# Motors_Drivers.net
KiCad netlist of a schematic drawn in Altium Designer
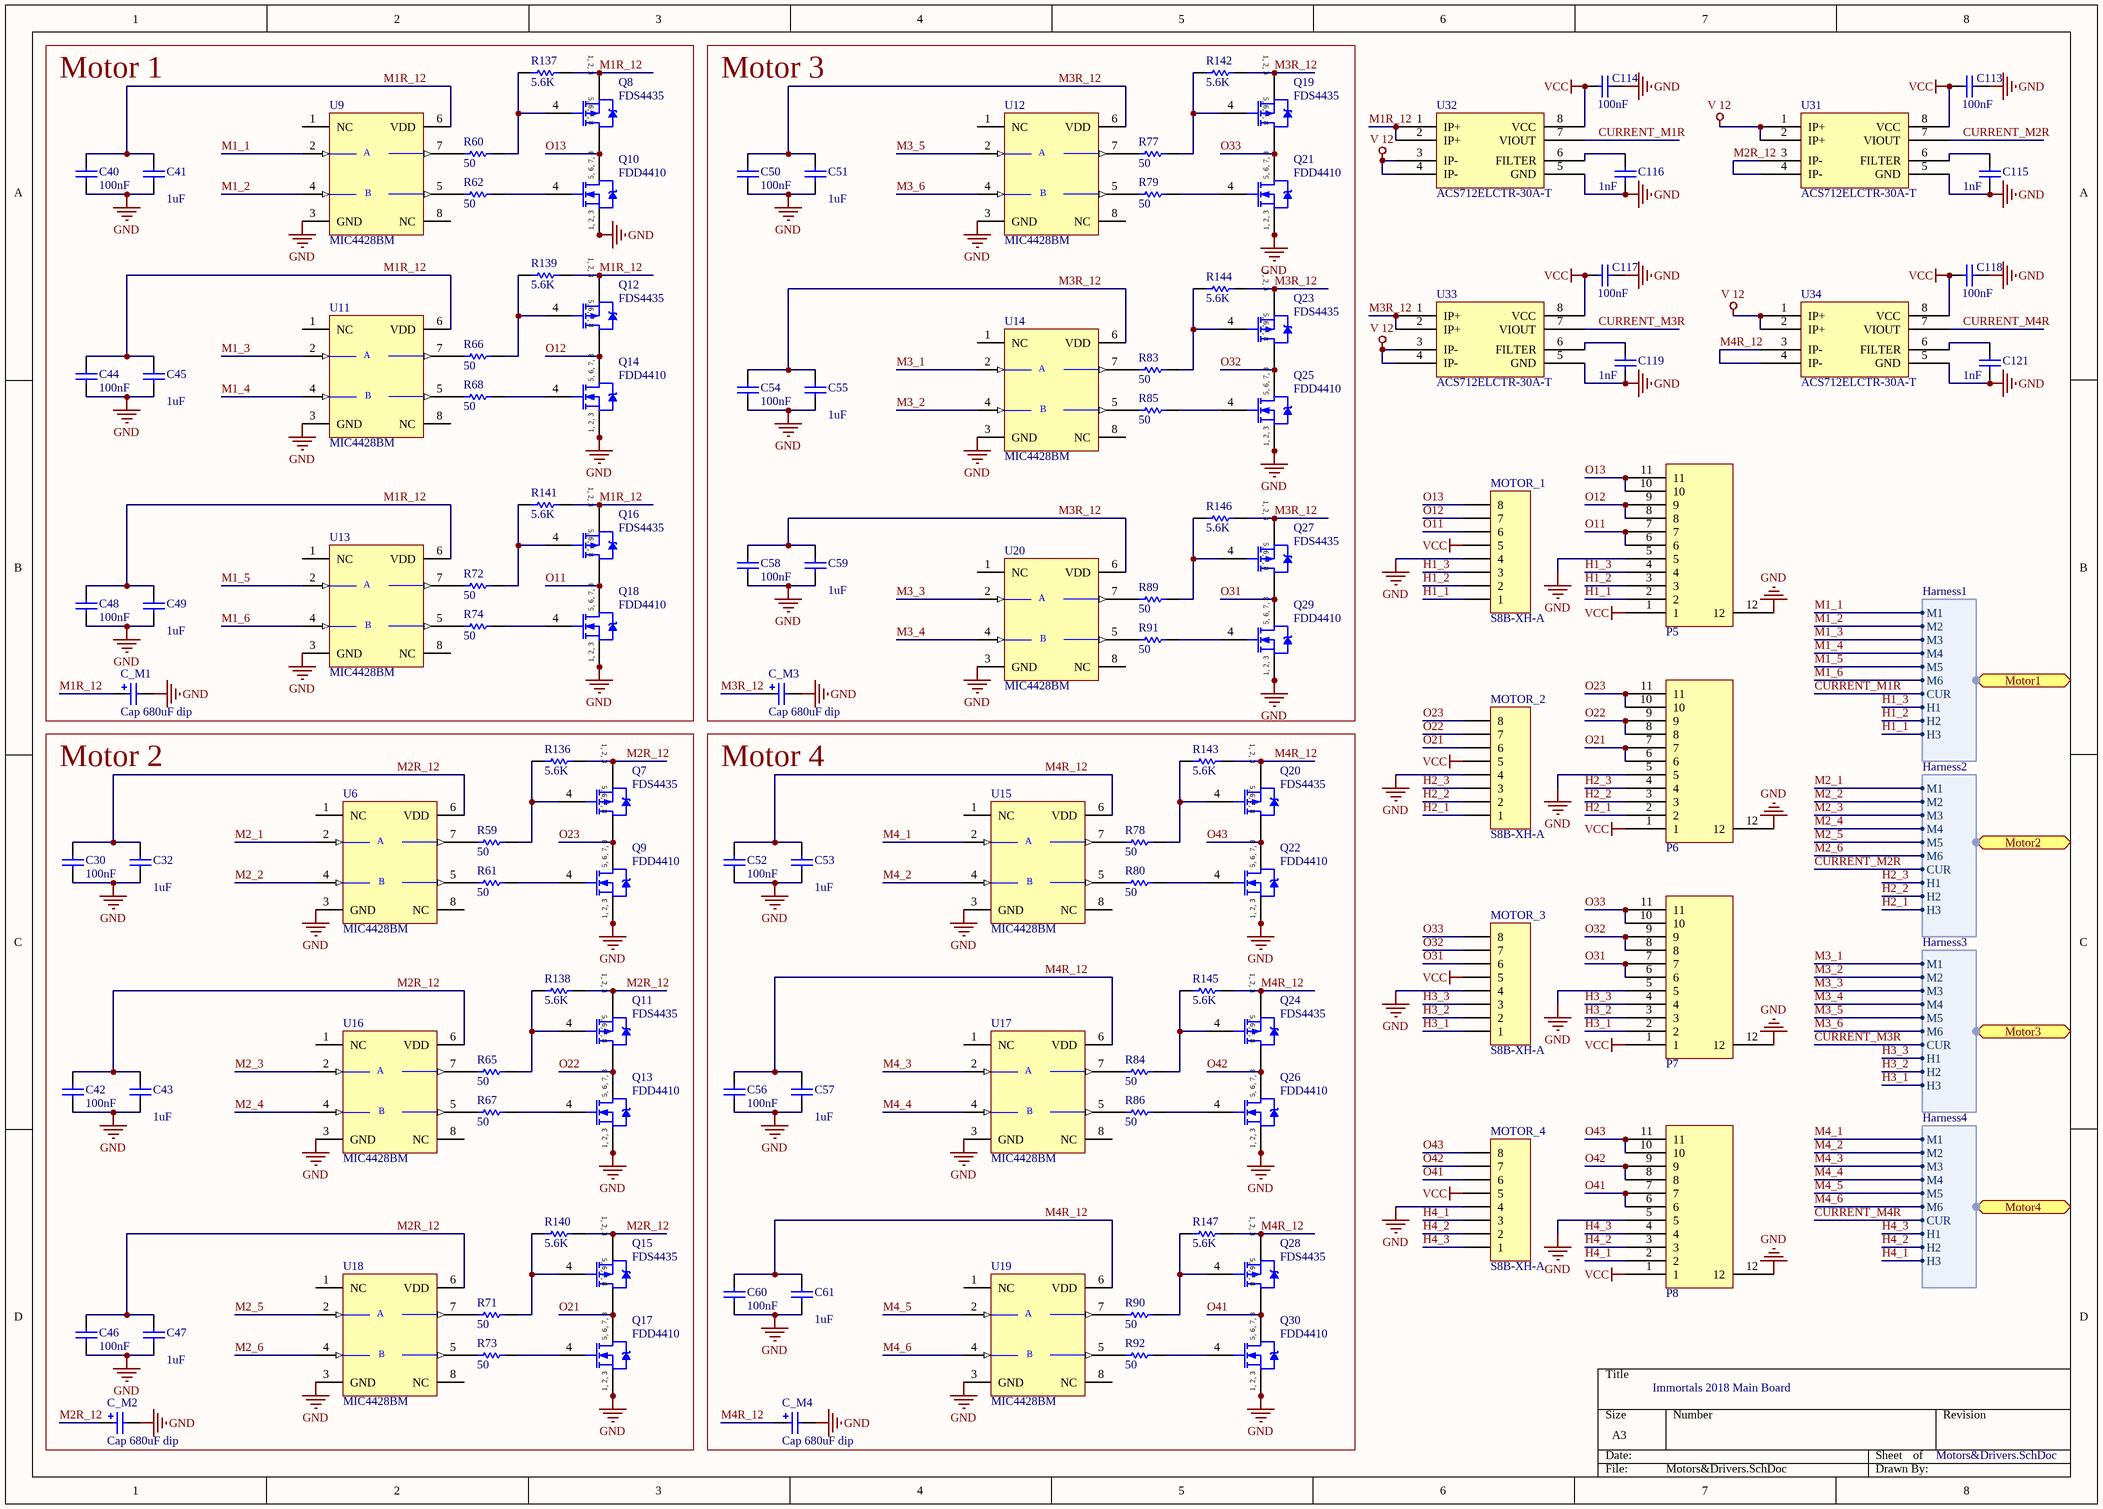
[diagram p0: Motors&Drivers.SchDoc]

(export (version "E")
  (design (tool "Eeschema 10.0.6"))
  (components
    (comp (ref "C30")
      (value "100nF")
      (footprint "1608[0603]")
      (description "Capacitor (Semiconductor SIM Model)")
      (fields (field (name "Comment") "Cap 100nF 0603") (field (name "PUBLISHER") "Altium Limited"))
      (libsource (lib "Miscellaneous Devices") (part "Cap Semi"))
    )
    (comp (ref "C32")
      (value "1uF")
      (footprint "1608[0603]")
      (description "Capacitor (Semiconductor SIM Model)")
      (fields (field (name "Comment") "Cap 1uF 0603") (field (name "PUBLISHER") "Altium Limited"))
      (libsource (lib "Miscellaneous Devices") (part "Cap Semi"))
    )
    (comp (ref "C40")
      (value "100nF")
      (footprint "1608[0603]")
      (description "Capacitor (Semiconductor SIM Model)")
      (fields (field (name "Comment") "Cap 100nF 0603") (field (name "PUBLISHER") "Altium Limited"))
      (libsource (lib "Miscellaneous Devices") (part "Cap Semi"))
    )
    (comp (ref "C41")
      (value "1uF")
      (footprint "1608[0603]")
      (description "Capacitor (Semiconductor SIM Model)")
      (fields (field (name "Comment") "Cap 1uF 0603") (field (name "PUBLISHER") "Altium Limited"))
      (libsource (lib "Miscellaneous Devices") (part "Cap Semi"))
    )
    (comp (ref "C42")
      (value "100nF")
      (footprint "1608[0603]")
      (description "Capacitor (Semiconductor SIM Model)")
      (fields (field (name "Comment") "Cap 100nF 0603") (field (name "PUBLISHER") "Altium Limited"))
      (libsource (lib "Miscellaneous Devices") (part "Cap Semi"))
    )
    (comp (ref "C43")
      (value "1uF")
      (footprint "1608[0603]")
      (description "Capacitor (Semiconductor SIM Model)")
      (fields (field (name "Comment") "Cap 1uF 0603") (field (name "PUBLISHER") "Altium Limited"))
      (libsource (lib "Miscellaneous Devices") (part "Cap Semi"))
    )
    (comp (ref "C44")
      (value "100nF")
      (footprint "1608[0603]")
      (description "Capacitor (Semiconductor SIM Model)")
      (fields (field (name "Comment") "Cap 100nF 0603") (field (name "PUBLISHER") "Altium Limited"))
      (libsource (lib "Miscellaneous Devices") (part "Cap Semi"))
    )
    (comp (ref "C45")
      (value "1uF")
      (footprint "1608[0603]")
      (description "Capacitor (Semiconductor SIM Model)")
      (fields (field (name "Comment") "Cap 1uF 0603") (field (name "PUBLISHER") "Altium Limited"))
      (libsource (lib "Miscellaneous Devices") (part "Cap Semi"))
    )
    (comp (ref "C46")
      (value "100nF")
      (footprint "1608[0603]")
      (description "Capacitor (Semiconductor SIM Model)")
      (fields (field (name "Comment") "Cap 100nF 0603") (field (name "PUBLISHER") "Altium Limited"))
      (libsource (lib "Miscellaneous Devices") (part "Cap Semi"))
    )
    (comp (ref "C47")
      (value "1uF")
      (footprint "1608[0603]")
      (description "Capacitor (Semiconductor SIM Model)")
      (fields (field (name "Comment") "Cap 1uF 0603") (field (name "PUBLISHER") "Altium Limited"))
      (libsource (lib "Miscellaneous Devices") (part "Cap Semi"))
    )
    (comp (ref "C48")
      (value "100nF")
      (footprint "1608[0603]")
      (description "Capacitor (Semiconductor SIM Model)")
      (fields (field (name "Comment") "Cap 100nF 0603") (field (name "PUBLISHER") "Altium Limited"))
      (libsource (lib "Miscellaneous Devices") (part "Cap Semi"))
    )
    (comp (ref "C49")
      (value "1uF")
      (footprint "1608[0603]")
      (description "Capacitor (Semiconductor SIM Model)")
      (fields (field (name "Comment") "Cap 1uF 0603") (field (name "PUBLISHER") "Altium Limited"))
      (libsource (lib "Miscellaneous Devices") (part "Cap Semi"))
    )
    (comp (ref "C50")
      (value "100nF")
      (footprint "1608[0603]")
      (description "Capacitor (Semiconductor SIM Model)")
      (fields (field (name "Comment") "Cap 100nF 0603") (field (name "PUBLISHER") "Altium Limited"))
      (libsource (lib "Miscellaneous Devices") (part "Cap Semi"))
    )
    (comp (ref "C51")
      (value "1uF")
      (footprint "1608[0603]")
      (description "Capacitor (Semiconductor SIM Model)")
      (fields (field (name "Comment") "Cap 1uF 0603") (field (name "PUBLISHER") "Altium Limited"))
      (libsource (lib "Miscellaneous Devices") (part "Cap Semi"))
    )
    (comp (ref "C52")
      (value "100nF")
      (footprint "1608[0603]")
      (description "Capacitor (Semiconductor SIM Model)")
      (fields (field (name "Comment") "Cap 100nF 0603") (field (name "PUBLISHER") "Altium Limited"))
      (libsource (lib "Miscellaneous Devices") (part "Cap Semi"))
    )
    (comp (ref "C53")
      (value "1uF")
      (footprint "1608[0603]")
      (description "Capacitor (Semiconductor SIM Model)")
      (fields (field (name "Comment") "Cap 1uF 0603") (field (name "PUBLISHER") "Altium Limited"))
      (libsource (lib "Miscellaneous Devices") (part "Cap Semi"))
    )
    (comp (ref "C54")
      (value "100nF")
      (footprint "1608[0603]")
      (description "Capacitor (Semiconductor SIM Model)")
      (fields (field (name "Comment") "Cap 100nF 0603") (field (name "PUBLISHER") "Altium Limited"))
      (libsource (lib "Miscellaneous Devices") (part "Cap Semi"))
    )
    (comp (ref "C55")
      (value "1uF")
      (footprint "1608[0603]")
      (description "Capacitor (Semiconductor SIM Model)")
      (fields (field (name "Comment") "Cap 1uF 0603") (field (name "PUBLISHER") "Altium Limited"))
      (libsource (lib "Miscellaneous Devices") (part "Cap Semi"))
    )
    (comp (ref "C56")
      (value "100nF")
      (footprint "1608[0603]")
      (description "Capacitor (Semiconductor SIM Model)")
      (fields (field (name "Comment") "Cap 100nF 0603") (field (name "PUBLISHER") "Altium Limited"))
      (libsource (lib "Miscellaneous Devices") (part "Cap Semi"))
    )
    (comp (ref "C57")
      (value "1uF")
      (footprint "1608[0603]")
      (description "Capacitor (Semiconductor SIM Model)")
      (fields (field (name "Comment") "Cap 1uF 0603") (field (name "PUBLISHER") "Altium Limited"))
      (libsource (lib "Miscellaneous Devices") (part "Cap Semi"))
    )
    (comp (ref "C58")
      (value "100nF")
      (footprint "1608[0603]")
      (description "Capacitor (Semiconductor SIM Model)")
      (fields (field (name "Comment") "Cap 100nF 0603") (field (name "PUBLISHER") "Altium Limited"))
      (libsource (lib "Miscellaneous Devices") (part "Cap Semi"))
    )
    (comp (ref "C59")
      (value "1uF")
      (footprint "1608[0603]")
      (description "Capacitor (Semiconductor SIM Model)")
      (fields (field (name "Comment") "Cap 1uF 0603") (field (name "PUBLISHER") "Altium Limited"))
      (libsource (lib "Miscellaneous Devices") (part "Cap Semi"))
    )
    (comp (ref "C60")
      (value "100nF")
      (footprint "1608[0603]")
      (description "Capacitor (Semiconductor SIM Model)")
      (fields (field (name "Comment") "Cap 100nF 0603") (field (name "PUBLISHER") "Altium Limited"))
      (libsource (lib "Miscellaneous Devices") (part "Cap Semi"))
    )
    (comp (ref "C61")
      (value "1uF")
      (footprint "1608[0603]")
      (description "Capacitor (Semiconductor SIM Model)")
      (fields (field (name "Comment") "Cap 1uF 0603") (field (name "PUBLISHER") "Altium Limited"))
      (libsource (lib "Miscellaneous Devices") (part "Cap Semi"))
    )
    (comp (ref "C113")
      (value "100nF")
      (footprint "1608[0603]")
      (description "Capacitor (Semiconductor SIM Model)")
      (fields (field (name "Comment") "Cap 100nF 0603") (field (name "PUBLISHER") "Altium Limited"))
      (libsource (lib "Miscellaneous Devices") (part "Cap Semi"))
    )
    (comp (ref "C114")
      (value "100nF")
      (footprint "1608[0603]")
      (description "Capacitor (Semiconductor SIM Model)")
      (fields (field (name "Comment") "Cap 100nF 0603") (field (name "PUBLISHER") "Altium Limited"))
      (libsource (lib "Miscellaneous Devices") (part "Cap Semi"))
    )
    (comp (ref "C115")
      (value "1nF")
      (footprint "1608[0603]")
      (description "Capacitor (Semiconductor SIM Model)")
      (fields (field (name "Comment") "Cap 1nF 0603") (field (name "PUBLISHER") "Altium Limited"))
      (libsource (lib "Miscellaneous Devices") (part "Cap Semi"))
    )
    (comp (ref "C116")
      (value "1nF")
      (footprint "1608[0603]")
      (description "Capacitor (Semiconductor SIM Model)")
      (fields (field (name "Comment") "Cap 1nF 0603") (field (name "PUBLISHER") "Altium Limited"))
      (libsource (lib "Miscellaneous Devices") (part "Cap Semi"))
    )
    (comp (ref "C117")
      (value "100nF")
      (footprint "1608[0603]")
      (description "Capacitor (Semiconductor SIM Model)")
      (fields (field (name "Comment") "Cap 100nF 0603") (field (name "PUBLISHER") "Altium Limited"))
      (libsource (lib "Miscellaneous Devices") (part "Cap Semi"))
    )
    (comp (ref "C118")
      (value "100nF")
      (footprint "1608[0603]")
      (description "Capacitor (Semiconductor SIM Model)")
      (fields (field (name "Comment") "Cap 100nF 0603") (field (name "PUBLISHER") "Altium Limited"))
      (libsource (lib "Miscellaneous Devices") (part "Cap Semi"))
    )
    (comp (ref "C119")
      (value "1nF")
      (footprint "1608[0603]")
      (description "Capacitor (Semiconductor SIM Model)")
      (fields (field (name "Comment") "Cap 1nF 0603") (field (name "PUBLISHER") "Altium Limited"))
      (libsource (lib "Miscellaneous Devices") (part "Cap Semi"))
    )
    (comp (ref "C121")
      (value "1nF")
      (footprint "1608[0603]")
      (description "Capacitor (Semiconductor SIM Model)")
      (fields (field (name "Comment") "Cap 1nF 0603") (field (name "PUBLISHER") "Altium Limited"))
      (libsource (lib "Miscellaneous Devices") (part "Cap Semi"))
    )
    (comp (ref "C_M1")
      (value "Cap 680uF dip")
      (footprint "CAPPR5-5x5")
      (description "Polarized Capacitor (Radial)")
      (fields (field (name "PUBLISHER") "Altium Limited"))
      (libsource (lib "REV(5)") (part "Cap Pol1"))
    )
    (comp (ref "C_M2")
      (value "Cap 680uF dip")
      (footprint "CAPPR5-5x5")
      (description "Polarized Capacitor (Radial)")
      (fields (field (name "PUBLISHER") "Altium Limited"))
      (libsource (lib "REV(5)") (part "Cap Pol1"))
    )
    (comp (ref "C_M3")
      (value "Cap 680uF dip")
      (footprint "CAPPR5-5x5")
      (description "Polarized Capacitor (Radial)")
      (fields (field (name "PUBLISHER") "Altium Limited"))
      (libsource (lib "REV(5)") (part "Cap Pol1"))
    )
    (comp (ref "C_M4")
      (value "Cap 680uF dip")
      (footprint "CAPPR5-5x5")
      (description "Polarized Capacitor (Radial)")
      (fields (field (name "PUBLISHER") "Altium Limited"))
      (libsource (lib "REV(5)") (part "Cap Pol1"))
    )
    (comp (ref "MOTOR_1")
      (value "S8B-XH-A")
      (footprint "S8B-XH-A-1")
      (libsource (lib "REV(5)") (part "8pin XH"))
    )
    (comp (ref "MOTOR_2")
      (value "S8B-XH-A")
      (footprint "S8B-XH-A-1")
      (libsource (lib "REV(5)") (part "8pin XH"))
    )
    (comp (ref "MOTOR_3")
      (value "S8B-XH-A")
      (footprint "S8B-XH-A-1")
      (libsource (lib "REV(5)") (part "8pin XH"))
    )
    (comp (ref "MOTOR_4")
      (value "S8B-XH-A")
      (footprint "S8B-XH-A-1")
      (libsource (lib "REV(5)") (part "8pin XH"))
    )
    (comp (ref "P5")
      (value "TYCO")
      (footprint "TYCO")
      (description "11-pin Bottom Contact 30W Motor connector")
      (libsource (lib "REV(5)") (part "TYCO"))
    )
    (comp (ref "P6")
      (value "TYCO")
      (footprint "TYCO")
      (description "11-pin Bottom Contact 30W Motor connector")
      (libsource (lib "REV(5)") (part "TYCO"))
    )
    (comp (ref "P7")
      (value "TYCO")
      (footprint "TYCO")
      (description "11-pin Bottom Contact 30W Motor connector")
      (libsource (lib "REV(5)") (part "TYCO"))
    )
    (comp (ref "P8")
      (value "TYCO")
      (footprint "TYCO")
      (description "11-pin Bottom Contact 30W Motor connector")
      (libsource (lib "REV(5)") (part "TYCO"))
    )
    (comp (ref "Q7")
      (value "FDS4435")
      (footprint "SO-8_L")
      (description "HEXFET Power MOSFET")
      (fields (field (name "PUBLISHER") "Altium Limited"))
      (libsource (lib "IR Discrete MOSFET - Power") (part "IRF7204"))
    )
    (comp (ref "Q8")
      (value "FDS4435")
      (footprint "SO-8_L")
      (description "HEXFET Power MOSFET")
      (fields (field (name "PUBLISHER") "Altium Limited"))
      (libsource (lib "IR Discrete MOSFET - Power") (part "IRF7204"))
    )
    (comp (ref "Q9")
      (value "FDD4410")
      (footprint "SO-8_L")
      (description "HEXFET Power MOSFET")
      (fields (field (name "PUBLISHER") "Altium Limited"))
      (libsource (lib "IR Discrete MOSFET - Power") (part "IRF7201"))
    )
    (comp (ref "Q10")
      (value "FDD4410")
      (footprint "SO-8_L")
      (description "HEXFET Power MOSFET")
      (fields (field (name "PUBLISHER") "Altium Limited"))
      (libsource (lib "IR Discrete MOSFET - Power") (part "IRF7201"))
    )
    (comp (ref "Q11")
      (value "FDS4435")
      (footprint "SO-8_L")
      (description "HEXFET Power MOSFET")
      (fields (field (name "PUBLISHER") "Altium Limited"))
      (libsource (lib "IR Discrete MOSFET - Power") (part "IRF7204"))
    )
    (comp (ref "Q12")
      (value "FDS4435")
      (footprint "SO-8_L")
      (description "HEXFET Power MOSFET")
      (fields (field (name "PUBLISHER") "Altium Limited"))
      (libsource (lib "IR Discrete MOSFET - Power") (part "IRF7204"))
    )
    (comp (ref "Q13")
      (value "FDD4410")
      (footprint "SO-8_L")
      (description "HEXFET Power MOSFET")
      (fields (field (name "PUBLISHER") "Altium Limited"))
      (libsource (lib "IR Discrete MOSFET - Power") (part "IRF7201"))
    )
    (comp (ref "Q14")
      (value "FDD4410")
      (footprint "SO-8_L")
      (description "HEXFET Power MOSFET")
      (fields (field (name "PUBLISHER") "Altium Limited"))
      (libsource (lib "IR Discrete MOSFET - Power") (part "IRF7201"))
    )
    (comp (ref "Q15")
      (value "FDS4435")
      (footprint "SO-8_L")
      (description "HEXFET Power MOSFET")
      (fields (field (name "PUBLISHER") "Altium Limited"))
      (libsource (lib "IR Discrete MOSFET - Power") (part "IRF7204"))
    )
    (comp (ref "Q16")
      (value "FDS4435")
      (footprint "SO-8_L")
      (description "HEXFET Power MOSFET")
      (fields (field (name "PUBLISHER") "Altium Limited"))
      (libsource (lib "IR Discrete MOSFET - Power") (part "IRF7204"))
    )
    (comp (ref "Q17")
      (value "FDD4410")
      (footprint "SO-8_L")
      (description "HEXFET Power MOSFET")
      (fields (field (name "PUBLISHER") "Altium Limited"))
      (libsource (lib "IR Discrete MOSFET - Power") (part "IRF7201"))
    )
    (comp (ref "Q18")
      (value "FDD4410")
      (footprint "SO-8_L")
      (description "HEXFET Power MOSFET")
      (fields (field (name "PUBLISHER") "Altium Limited"))
      (libsource (lib "IR Discrete MOSFET - Power") (part "IRF7201"))
    )
    (comp (ref "Q19")
      (value "FDS4435")
      (footprint "SO-8_L")
      (description "HEXFET Power MOSFET")
      (fields (field (name "PUBLISHER") "Altium Limited"))
      (libsource (lib "IR Discrete MOSFET - Power") (part "IRF7204"))
    )
    (comp (ref "Q20")
      (value "FDS4435")
      (footprint "SO-8_L")
      (description "HEXFET Power MOSFET")
      (fields (field (name "PUBLISHER") "Altium Limited"))
      (libsource (lib "IR Discrete MOSFET - Power") (part "IRF7204"))
    )
    (comp (ref "Q21")
      (value "FDD4410")
      (footprint "SO-8_L")
      (description "HEXFET Power MOSFET")
      (fields (field (name "PUBLISHER") "Altium Limited"))
      (libsource (lib "IR Discrete MOSFET - Power") (part "IRF7201"))
    )
    (comp (ref "Q22")
      (value "FDD4410")
      (footprint "SO-8_L")
      (description "HEXFET Power MOSFET")
      (fields (field (name "PUBLISHER") "Altium Limited"))
      (libsource (lib "IR Discrete MOSFET - Power") (part "IRF7201"))
    )
    (comp (ref "Q23")
      (value "FDS4435")
      (footprint "SO-8_L")
      (description "HEXFET Power MOSFET")
      (fields (field (name "PUBLISHER") "Altium Limited"))
      (libsource (lib "IR Discrete MOSFET - Power") (part "IRF7204"))
    )
    (comp (ref "Q24")
      (value "FDS4435")
      (footprint "SO-8_L")
      (description "HEXFET Power MOSFET")
      (fields (field (name "PUBLISHER") "Altium Limited"))
      (libsource (lib "IR Discrete MOSFET - Power") (part "IRF7204"))
    )
    (comp (ref "Q25")
      (value "FDD4410")
      (footprint "SO-8_L")
      (description "HEXFET Power MOSFET")
      (fields (field (name "PUBLISHER") "Altium Limited"))
      (libsource (lib "IR Discrete MOSFET - Power") (part "IRF7201"))
    )
    (comp (ref "Q26")
      (value "FDD4410")
      (footprint "SO-8_L")
      (description "HEXFET Power MOSFET")
      (fields (field (name "PUBLISHER") "Altium Limited"))
      (libsource (lib "IR Discrete MOSFET - Power") (part "IRF7201"))
    )
    (comp (ref "Q27")
      (value "FDS4435")
      (footprint "SO-8_L")
      (description "HEXFET Power MOSFET")
      (fields (field (name "PUBLISHER") "Altium Limited"))
      (libsource (lib "IR Discrete MOSFET - Power") (part "IRF7204"))
    )
    (comp (ref "Q28")
      (value "FDS4435")
      (footprint "SO-8_L")
      (description "HEXFET Power MOSFET")
      (fields (field (name "PUBLISHER") "Altium Limited"))
      (libsource (lib "IR Discrete MOSFET - Power") (part "IRF7204"))
    )
    (comp (ref "Q29")
      (value "FDD4410")
      (footprint "SO-8_L")
      (description "HEXFET Power MOSFET")
      (fields (field (name "PUBLISHER") "Altium Limited"))
      (libsource (lib "IR Discrete MOSFET - Power") (part "IRF7201"))
    )
    (comp (ref "Q30")
      (value "FDD4410")
      (footprint "SO-8_L")
      (description "HEXFET Power MOSFET")
      (fields (field (name "PUBLISHER") "Altium Limited"))
      (libsource (lib "IR Discrete MOSFET - Power") (part "IRF7201"))
    )
    (comp (ref "R59")
      (value "50")
      (footprint "1608[0603]")
      (description "Semiconductor Resistor")
      (fields (field (name "Comment") "Res 50 0603") (field (name "PUBLISHER") "Altium Limited"))
      (libsource (lib "Miscellaneous Devices") (part "Res Semi"))
    )
    (comp (ref "R60")
      (value "50")
      (footprint "1608[0603]")
      (description "Semiconductor Resistor")
      (fields (field (name "Comment") "Res 50 0603") (field (name "PUBLISHER") "Altium Limited"))
      (libsource (lib "Miscellaneous Devices") (part "Res Semi"))
    )
    (comp (ref "R61")
      (value "50")
      (footprint "1608[0603]")
      (description "Semiconductor Resistor")
      (fields (field (name "Comment") "Res 50 0603") (field (name "PUBLISHER") "Altium Limited"))
      (libsource (lib "Miscellaneous Devices") (part "Res Semi"))
    )
    (comp (ref "R62")
      (value "50")
      (footprint "1608[0603]")
      (description "Semiconductor Resistor")
      (fields (field (name "Comment") "Res 50 0603") (field (name "PUBLISHER") "Altium Limited"))
      (libsource (lib "Miscellaneous Devices") (part "Res Semi"))
    )
    (comp (ref "R65")
      (value "50")
      (footprint "1608[0603]")
      (description "Semiconductor Resistor")
      (fields (field (name "Comment") "Res 50 0603") (field (name "PUBLISHER") "Altium Limited"))
      (libsource (lib "Miscellaneous Devices") (part "Res Semi"))
    )
    (comp (ref "R66")
      (value "50")
      (footprint "1608[0603]")
      (description "Semiconductor Resistor")
      (fields (field (name "Comment") "Res 50 0603") (field (name "PUBLISHER") "Altium Limited"))
      (libsource (lib "Miscellaneous Devices") (part "Res Semi"))
    )
    (comp (ref "R67")
      (value "50")
      (footprint "1608[0603]")
      (description "Semiconductor Resistor")
      (fields (field (name "Comment") "Res 50 0603") (field (name "PUBLISHER") "Altium Limited"))
      (libsource (lib "Miscellaneous Devices") (part "Res Semi"))
    )
    (comp (ref "R68")
      (value "50")
      (footprint "1608[0603]")
      (description "Semiconductor Resistor")
      (fields (field (name "Comment") "Res 50 0603") (field (name "PUBLISHER") "Altium Limited"))
      (libsource (lib "Miscellaneous Devices") (part "Res Semi"))
    )
    (comp (ref "R71")
      (value "50")
      (footprint "1608[0603]")
      (description "Semiconductor Resistor")
      (fields (field (name "Comment") "Res 50 0603") (field (name "PUBLISHER") "Altium Limited"))
      (libsource (lib "Miscellaneous Devices") (part "Res Semi"))
    )
    (comp (ref "R72")
      (value "50")
      (footprint "1608[0603]")
      (description "Semiconductor Resistor")
      (fields (field (name "Comment") "Res 50 0603") (field (name "PUBLISHER") "Altium Limited"))
      (libsource (lib "Miscellaneous Devices") (part "Res Semi"))
    )
    (comp (ref "R73")
      (value "50")
      (footprint "1608[0603]")
      (description "Semiconductor Resistor")
      (fields (field (name "Comment") "Res 50 0603") (field (name "PUBLISHER") "Altium Limited"))
      (libsource (lib "Miscellaneous Devices") (part "Res Semi"))
    )
    (comp (ref "R74")
      (value "50")
      (footprint "1608[0603]")
      (description "Semiconductor Resistor")
      (fields (field (name "Comment") "Res 50 0603") (field (name "PUBLISHER") "Altium Limited"))
      (libsource (lib "Miscellaneous Devices") (part "Res Semi"))
    )
    (comp (ref "R77")
      (value "50")
      (footprint "1608[0603]")
      (description "Semiconductor Resistor")
      (fields (field (name "Comment") "Res 50 0603") (field (name "PUBLISHER") "Altium Limited"))
      (libsource (lib "Miscellaneous Devices") (part "Res Semi"))
    )
    (comp (ref "R78")
      (value "50")
      (footprint "1608[0603]")
      (description "Semiconductor Resistor")
      (fields (field (name "Comment") "Res 50 0603") (field (name "PUBLISHER") "Altium Limited"))
      (libsource (lib "Miscellaneous Devices") (part "Res Semi"))
    )
    (comp (ref "R79")
      (value "50")
      (footprint "1608[0603]")
      (description "Semiconductor Resistor")
      (fields (field (name "Comment") "Res 50 0603") (field (name "PUBLISHER") "Altium Limited"))
      (libsource (lib "Miscellaneous Devices") (part "Res Semi"))
    )
    (comp (ref "R80")
      (value "50")
      (footprint "1608[0603]")
      (description "Semiconductor Resistor")
      (fields (field (name "Comment") "Res 50 0603") (field (name "PUBLISHER") "Altium Limited"))
      (libsource (lib "Miscellaneous Devices") (part "Res Semi"))
    )
    (comp (ref "R83")
      (value "50")
      (footprint "1608[0603]")
      (description "Semiconductor Resistor")
      (fields (field (name "Comment") "Res 50 0603") (field (name "PUBLISHER") "Altium Limited"))
      (libsource (lib "Miscellaneous Devices") (part "Res Semi"))
    )
    (comp (ref "R84")
      (value "50")
      (footprint "1608[0603]")
      (description "Semiconductor Resistor")
      (fields (field (name "Comment") "Res 50 0603") (field (name "PUBLISHER") "Altium Limited"))
      (libsource (lib "Miscellaneous Devices") (part "Res Semi"))
    )
    (comp (ref "R85")
      (value "50")
      (footprint "1608[0603]")
      (description "Semiconductor Resistor")
      (fields (field (name "Comment") "Res 50 0603") (field (name "PUBLISHER") "Altium Limited"))
      (libsource (lib "Miscellaneous Devices") (part "Res Semi"))
    )
    (comp (ref "R86")
      (value "50")
      (footprint "1608[0603]")
      (description "Semiconductor Resistor")
      (fields (field (name "Comment") "Res 50 0603") (field (name "PUBLISHER") "Altium Limited"))
      (libsource (lib "Miscellaneous Devices") (part "Res Semi"))
    )
    (comp (ref "R89")
      (value "50")
      (footprint "1608[0603]")
      (description "Semiconductor Resistor")
      (fields (field (name "Comment") "Res 50 0603") (field (name "PUBLISHER") "Altium Limited"))
      (libsource (lib "Miscellaneous Devices") (part "Res Semi"))
    )
    (comp (ref "R90")
      (value "50")
      (footprint "1608[0603]")
      (description "Semiconductor Resistor")
      (fields (field (name "Comment") "Res 50 0603") (field (name "PUBLISHER") "Altium Limited"))
      (libsource (lib "Miscellaneous Devices") (part "Res Semi"))
    )
    (comp (ref "R91")
      (value "50")
      (footprint "1608[0603]")
      (description "Semiconductor Resistor")
      (fields (field (name "Comment") "Res 50 0603") (field (name "PUBLISHER") "Altium Limited"))
      (libsource (lib "Miscellaneous Devices") (part "Res Semi"))
    )
    (comp (ref "R92")
      (value "50")
      (footprint "1608[0603]")
      (description "Semiconductor Resistor")
      (fields (field (name "Comment") "Res 50 0603") (field (name "PUBLISHER") "Altium Limited"))
      (libsource (lib "Miscellaneous Devices") (part "Res Semi"))
    )
    (comp (ref "R136")
      (value "5.6K")
      (footprint "1608[0603]")
      (description "Semiconductor Resistor")
      (fields (field (name "Comment") "Res 5.6K 0603") (field (name "PUBLISHER") "Altium Limited"))
      (libsource (lib "Miscellaneous Devices") (part "Res Semi"))
    )
    (comp (ref "R137")
      (value "5.6K")
      (footprint "1608[0603]")
      (description "Semiconductor Resistor")
      (fields (field (name "Comment") "Res 5.6K 0603") (field (name "PUBLISHER") "Altium Limited"))
      (libsource (lib "Miscellaneous Devices") (part "Res Semi"))
    )
    (comp (ref "R138")
      (value "5.6K")
      (footprint "1608[0603]")
      (description "Semiconductor Resistor")
      (fields (field (name "Comment") "Res 5.6K 0603") (field (name "PUBLISHER") "Altium Limited"))
      (libsource (lib "Miscellaneous Devices") (part "Res Semi"))
    )
    (comp (ref "R139")
      (value "5.6K")
      (footprint "1608[0603]")
      (description "Semiconductor Resistor")
      (fields (field (name "Comment") "Res 5.6K 0603") (field (name "PUBLISHER") "Altium Limited"))
      (libsource (lib "Miscellaneous Devices") (part "Res Semi"))
    )
    (comp (ref "R140")
      (value "5.6K")
      (footprint "1608[0603]")
      (description "Semiconductor Resistor")
      (fields (field (name "Comment") "Res 5.6K 0603") (field (name "PUBLISHER") "Altium Limited"))
      (libsource (lib "Miscellaneous Devices") (part "Res Semi"))
    )
    (comp (ref "R141")
      (value "5.6K")
      (footprint "1608[0603]")
      (description "Semiconductor Resistor")
      (fields (field (name "Comment") "Res 5.6K 0603") (field (name "PUBLISHER") "Altium Limited"))
      (libsource (lib "Miscellaneous Devices") (part "Res Semi"))
    )
    (comp (ref "R142")
      (value "5.6K")
      (footprint "1608[0603]")
      (description "Semiconductor Resistor")
      (fields (field (name "Comment") "Res 5.6K 0603") (field (name "PUBLISHER") "Altium Limited"))
      (libsource (lib "Miscellaneous Devices") (part "Res Semi"))
    )
    (comp (ref "R143")
      (value "5.6K")
      (footprint "1608[0603]")
      (description "Semiconductor Resistor")
      (fields (field (name "Comment") "Res 5.6K 0603") (field (name "PUBLISHER") "Altium Limited"))
      (libsource (lib "Miscellaneous Devices") (part "Res Semi"))
    )
    (comp (ref "R144")
      (value "5.6K")
      (footprint "1608[0603]")
      (description "Semiconductor Resistor")
      (fields (field (name "Comment") "Res 5.6K 0603") (field (name "PUBLISHER") "Altium Limited"))
      (libsource (lib "Miscellaneous Devices") (part "Res Semi"))
    )
    (comp (ref "R145")
      (value "5.6K")
      (footprint "1608[0603]")
      (description "Semiconductor Resistor")
      (fields (field (name "Comment") "Res 5.6K 0603") (field (name "PUBLISHER") "Altium Limited"))
      (libsource (lib "Miscellaneous Devices") (part "Res Semi"))
    )
    (comp (ref "R146")
      (value "5.6K")
      (footprint "1608[0603]")
      (description "Semiconductor Resistor")
      (fields (field (name "Comment") "Res 5.6K 0603") (field (name "PUBLISHER") "Altium Limited"))
      (libsource (lib "Miscellaneous Devices") (part "Res Semi"))
    )
    (comp (ref "R147")
      (value "5.6K")
      (footprint "1608[0603]")
      (description "Semiconductor Resistor")
      (fields (field (name "Comment") "Res 5.6K 0603") (field (name "PUBLISHER") "Altium Limited"))
      (libsource (lib "Miscellaneous Devices") (part "Res Semi"))
    )
    (comp (ref "U6")
      (value "MIC4428BM")
      (footprint "NSO8_L")
      (description "Dual High-Speed 1.5A MOSFET Driver")
      (fields (field (name "PUBLISHER") "Altium Limited"))
      (libsource (lib "Maxim Interface MOSFET Driver") (part "MAX4427CSA"))
    )
    (comp (ref "U9")
      (value "MIC4428BM")
      (footprint "NSO8_L")
      (description "Dual High-Speed 1.5A MOSFET Driver")
      (fields (field (name "PUBLISHER") "Altium Limited"))
      (libsource (lib "Maxim Interface MOSFET Driver") (part "MAX4427CSA"))
    )
    (comp (ref "U11")
      (value "MIC4428BM")
      (footprint "NSO8_L")
      (description "Dual High-Speed 1.5A MOSFET Driver")
      (fields (field (name "PUBLISHER") "Altium Limited"))
      (libsource (lib "Maxim Interface MOSFET Driver") (part "MAX4427CSA"))
    )
    (comp (ref "U12")
      (value "MIC4428BM")
      (footprint "NSO8_L")
      (description "Dual High-Speed 1.5A MOSFET Driver")
      (fields (field (name "PUBLISHER") "Altium Limited"))
      (libsource (lib "Maxim Interface MOSFET Driver") (part "MAX4427CSA"))
    )
    (comp (ref "U13")
      (value "MIC4428BM")
      (footprint "NSO8_L")
      (description "Dual High-Speed 1.5A MOSFET Driver")
      (fields (field (name "PUBLISHER") "Altium Limited"))
      (libsource (lib "Maxim Interface MOSFET Driver") (part "MAX4427CSA"))
    )
    (comp (ref "U14")
      (value "MIC4428BM")
      (footprint "NSO8_L")
      (description "Dual High-Speed 1.5A MOSFET Driver")
      (fields (field (name "PUBLISHER") "Altium Limited"))
      (libsource (lib "Maxim Interface MOSFET Driver") (part "MAX4427CSA"))
    )
    (comp (ref "U15")
      (value "MIC4428BM")
      (footprint "NSO8_L")
      (description "Dual High-Speed 1.5A MOSFET Driver")
      (fields (field (name "PUBLISHER") "Altium Limited"))
      (libsource (lib "Maxim Interface MOSFET Driver") (part "MAX4427CSA"))
    )
    (comp (ref "U16")
      (value "MIC4428BM")
      (footprint "NSO8_L")
      (description "Dual High-Speed 1.5A MOSFET Driver")
      (fields (field (name "PUBLISHER") "Altium Limited"))
      (libsource (lib "Maxim Interface MOSFET Driver") (part "MAX4427CSA"))
    )
    (comp (ref "U17")
      (value "MIC4428BM")
      (footprint "NSO8_L")
      (description "Dual High-Speed 1.5A MOSFET Driver")
      (fields (field (name "PUBLISHER") "Altium Limited"))
      (libsource (lib "Maxim Interface MOSFET Driver") (part "MAX4427CSA"))
    )
    (comp (ref "U18")
      (value "MIC4428BM")
      (footprint "NSO8_L")
      (description "Dual High-Speed 1.5A MOSFET Driver")
      (fields (field (name "PUBLISHER") "Altium Limited"))
      (libsource (lib "Maxim Interface MOSFET Driver") (part "MAX4427CSA"))
    )
    (comp (ref "U19")
      (value "MIC4428BM")
      (footprint "NSO8_L")
      (description "Dual High-Speed 1.5A MOSFET Driver")
      (fields (field (name "PUBLISHER") "Altium Limited"))
      (libsource (lib "Maxim Interface MOSFET Driver") (part "MAX4427CSA"))
    )
    (comp (ref "U20")
      (value "MIC4428BM")
      (footprint "NSO8_L")
      (description "Dual High-Speed 1.5A MOSFET Driver")
      (fields (field (name "PUBLISHER") "Altium Limited"))
      (libsource (lib "Maxim Interface MOSFET Driver") (part "MAX4427CSA"))
    )
    (comp (ref "U31")
      (value "ACS712ELCTR-30A-T")
      (footprint "SOIC_8")
      (libsource (lib "Mikona") (part "ACS712ELCTR-30A-T"))
    )
    (comp (ref "U32")
      (value "ACS712ELCTR-30A-T")
      (footprint "SOIC_8")
      (libsource (lib "Mikona") (part "ACS712ELCTR-30A-T"))
    )
    (comp (ref "U33")
      (value "ACS712ELCTR-30A-T")
      (footprint "SOIC_8")
      (libsource (lib "Mikona") (part "ACS712ELCTR-30A-T"))
    )
    (comp (ref "U34")
      (value "ACS712ELCTR-30A-T")
      (footprint "SOIC_8")
      (libsource (lib "Mikona") (part "ACS712ELCTR-30A-T"))
    )
  )
  (nets
    (net (code "5") (name "/CURRENT_M1R") (class "Default")
      (node (ref "U32") (pin "7") (pinfunction "VIOUT_7") (pintype "passive"))
    )
    (net (code "6") (name "/CURRENT_M2R") (class "Default")
      (node (ref "U31") (pin "7") (pinfunction "VIOUT_7") (pintype "passive"))
    )
    (net (code "7") (name "/CURRENT_M3R") (class "Default")
      (node (ref "U33") (pin "7") (pinfunction "VIOUT_7") (pintype "passive"))
    )
    (net (code "8") (name "/CURRENT_M4R") (class "Default")
      (node (ref "U34") (pin "7") (pinfunction "VIOUT_7") (pintype "passive"))
    )
    (net (code "9") (name "/H1_1") (class "Default")
      (node (ref "MOTOR_1") (pin "1") (pinfunction "1_1") (pintype "passive"))
      (node (ref "P5") (pin "2") (pinfunction "2_2") (pintype "passive"))
    )
    (net (code "10") (name "/H1_2") (class "Default")
      (node (ref "MOTOR_1") (pin "2") (pinfunction "2_2") (pintype "passive"))
      (node (ref "P5") (pin "3") (pinfunction "3_3") (pintype "passive"))
    )
    (net (code "11") (name "/H1_3") (class "Default")
      (node (ref "MOTOR_1") (pin "3") (pinfunction "3_3") (pintype "passive"))
      (node (ref "P5") (pin "4") (pinfunction "4_4") (pintype "passive"))
    )
    (net (code "12") (name "/H2_1") (class "Default")
      (node (ref "MOTOR_2") (pin "1") (pinfunction "1_1") (pintype "passive"))
      (node (ref "P6") (pin "2") (pinfunction "2_2") (pintype "passive"))
    )
    (net (code "13") (name "/H2_2") (class "Default")
      (node (ref "MOTOR_2") (pin "2") (pinfunction "2_2") (pintype "passive"))
      (node (ref "P6") (pin "3") (pinfunction "3_3") (pintype "passive"))
    )
    (net (code "14") (name "/H2_3") (class "Default")
      (node (ref "MOTOR_2") (pin "3") (pinfunction "3_3") (pintype "passive"))
      (node (ref "P6") (pin "4") (pinfunction "4_4") (pintype "passive"))
    )
    (net (code "15") (name "/H3_1") (class "Default")
      (node (ref "MOTOR_3") (pin "1") (pinfunction "1_1") (pintype "passive"))
      (node (ref "P7") (pin "2") (pinfunction "2_2") (pintype "passive"))
    )
    (net (code "16") (name "/H3_2") (class "Default")
      (node (ref "MOTOR_3") (pin "2") (pinfunction "2_2") (pintype "passive"))
      (node (ref "P7") (pin "3") (pinfunction "3_3") (pintype "passive"))
    )
    (net (code "17") (name "/H3_3") (class "Default")
      (node (ref "MOTOR_3") (pin "3") (pinfunction "3_3") (pintype "passive"))
      (node (ref "P7") (pin "4") (pinfunction "4_4") (pintype "passive"))
    )
    (net (code "18") (name "/H4_1") (class "Default")
      (node (ref "MOTOR_4") (pin "3") (pinfunction "3_3") (pintype "passive"))
      (node (ref "P8") (pin "2") (pinfunction "2_2") (pintype "passive"))
    )
    (net (code "19") (name "/H4_2") (class "Default")
      (node (ref "MOTOR_4") (pin "2") (pinfunction "2_2") (pintype "passive"))
      (node (ref "P8") (pin "3") (pinfunction "3_3") (pintype "passive"))
    )
    (net (code "20") (name "/H4_3") (class "Default")
      (node (ref "MOTOR_4") (pin "1") (pinfunction "1_1") (pintype "passive"))
      (node (ref "P8") (pin "4") (pinfunction "4_4") (pintype "passive"))
    )
    (net (code "21") (name "/M1R_12") (class "Default")
      (node (ref "C40") (pin "2") (pinfunction "2_2") (pintype "passive"))
      (node (ref "C41") (pin "2") (pinfunction "2_2") (pintype "passive"))
      (node (ref "C44") (pin "2") (pinfunction "2_2") (pintype "passive"))
      (node (ref "C45") (pin "2") (pinfunction "2_2") (pintype "passive"))
      (node (ref "C48") (pin "2") (pinfunction "2_2") (pintype "passive"))
      (node (ref "C49") (pin "2") (pinfunction "2_2") (pintype "passive"))
      (node (ref "C_M1") (pin "1") (pinfunction "1_1") (pintype "passive"))
      (node (ref "Q12") (pin "1") (pinfunction "S_1") (pintype "passive"))
      (node (ref "Q12") (pin "2") (pinfunction "S_2") (pintype "passive"))
      (node (ref "Q12") (pin "3") (pinfunction "S_3") (pintype "passive"))
      (node (ref "Q16") (pin "1") (pinfunction "S_1") (pintype "passive"))
      (node (ref "Q16") (pin "2") (pinfunction "S_2") (pintype "passive"))
      (node (ref "Q16") (pin "3") (pinfunction "S_3") (pintype "passive"))
      (node (ref "Q8") (pin "1") (pinfunction "S_1") (pintype "passive"))
      (node (ref "Q8") (pin "2") (pinfunction "S_2") (pintype "passive"))
      (node (ref "Q8") (pin "3") (pinfunction "S_3") (pintype "passive"))
      (node (ref "R137") (pin "1") (pinfunction "1_1") (pintype "passive"))
      (node (ref "R139") (pin "1") (pinfunction "1_1") (pintype "passive"))
      (node (ref "R141") (pin "1") (pinfunction "1_1") (pintype "passive"))
      (node (ref "U11") (pin "6") (pinfunction "VDD_6") (pintype "power_in"))
      (node (ref "U13") (pin "6") (pinfunction "VDD_6") (pintype "power_in"))
      (node (ref "U32") (pin "1") (pinfunction "IP+_1") (pintype "passive"))
      (node (ref "U32") (pin "2") (pinfunction "IP+_2") (pintype "passive"))
      (node (ref "U9") (pin "6") (pinfunction "VDD_6") (pintype "power_in"))
    )
    (net (code "22") (name "/M1_1") (class "Default")
      (node (ref "U9") (pin "2") (pinfunction "INA_2") (pintype "input"))
    )
    (net (code "23") (name "/M1_2") (class "Default")
      (node (ref "U9") (pin "4") (pinfunction "INB_4") (pintype "input"))
    )
    (net (code "24") (name "/M1_3") (class "Default")
      (node (ref "U11") (pin "2") (pinfunction "INA_2") (pintype "input"))
    )
    (net (code "25") (name "/M1_4") (class "Default")
      (node (ref "U11") (pin "4") (pinfunction "INB_4") (pintype "input"))
    )
    (net (code "26") (name "/M1_5") (class "Default")
      (node (ref "U13") (pin "2") (pinfunction "INA_2") (pintype "input"))
    )
    (net (code "27") (name "/M1_6") (class "Default")
      (node (ref "U13") (pin "4") (pinfunction "INB_4") (pintype "input"))
    )
    (net (code "28") (name "/M2R_12") (class "Default")
      (node (ref "C30") (pin "2") (pinfunction "2_2") (pintype "passive"))
      (node (ref "C32") (pin "2") (pinfunction "2_2") (pintype "passive"))
      (node (ref "C42") (pin "2") (pinfunction "2_2") (pintype "passive"))
      (node (ref "C43") (pin "2") (pinfunction "2_2") (pintype "passive"))
      (node (ref "C46") (pin "2") (pinfunction "2_2") (pintype "passive"))
      (node (ref "C47") (pin "2") (pinfunction "2_2") (pintype "passive"))
      (node (ref "C_M2") (pin "1") (pinfunction "1_1") (pintype "passive"))
      (node (ref "Q11") (pin "1") (pinfunction "S_1") (pintype "passive"))
      (node (ref "Q11") (pin "2") (pinfunction "S_2") (pintype "passive"))
      (node (ref "Q11") (pin "3") (pinfunction "S_3") (pintype "passive"))
      (node (ref "Q15") (pin "1") (pinfunction "S_1") (pintype "passive"))
      (node (ref "Q15") (pin "2") (pinfunction "S_2") (pintype "passive"))
      (node (ref "Q15") (pin "3") (pinfunction "S_3") (pintype "passive"))
      (node (ref "Q7") (pin "1") (pinfunction "S_1") (pintype "passive"))
      (node (ref "Q7") (pin "2") (pinfunction "S_2") (pintype "passive"))
      (node (ref "Q7") (pin "3") (pinfunction "S_3") (pintype "passive"))
      (node (ref "R136") (pin "1") (pinfunction "1_1") (pintype "passive"))
      (node (ref "R138") (pin "1") (pinfunction "1_1") (pintype "passive"))
      (node (ref "R140") (pin "1") (pinfunction "1_1") (pintype "passive"))
      (node (ref "U16") (pin "6") (pinfunction "VDD_6") (pintype "power_in"))
      (node (ref "U18") (pin "6") (pinfunction "VDD_6") (pintype "power_in"))
      (node (ref "U31") (pin "3") (pinfunction "IP-_3") (pintype "passive"))
      (node (ref "U31") (pin "4") (pinfunction "IP-_4") (pintype "passive"))
      (node (ref "U6") (pin "6") (pinfunction "VDD_6") (pintype "power_in"))
    )
    (net (code "29") (name "/M2_1") (class "Default")
      (node (ref "U6") (pin "2") (pinfunction "INA_2") (pintype "input"))
    )
    (net (code "30") (name "/M2_2") (class "Default")
      (node (ref "U6") (pin "4") (pinfunction "INB_4") (pintype "input"))
    )
    (net (code "31") (name "/M2_3") (class "Default")
      (node (ref "U16") (pin "2") (pinfunction "INA_2") (pintype "input"))
    )
    (net (code "32") (name "/M2_4") (class "Default")
      (node (ref "U16") (pin "4") (pinfunction "INB_4") (pintype "input"))
    )
    (net (code "33") (name "/M2_5") (class "Default")
      (node (ref "U18") (pin "2") (pinfunction "INA_2") (pintype "input"))
    )
    (net (code "34") (name "/M2_6") (class "Default")
      (node (ref "U18") (pin "4") (pinfunction "INB_4") (pintype "input"))
    )
    (net (code "35") (name "/M3R_12") (class "Default")
      (node (ref "C50") (pin "2") (pinfunction "2_2") (pintype "passive"))
      (node (ref "C51") (pin "2") (pinfunction "2_2") (pintype "passive"))
      (node (ref "C54") (pin "2") (pinfunction "2_2") (pintype "passive"))
      (node (ref "C55") (pin "2") (pinfunction "2_2") (pintype "passive"))
      (node (ref "C58") (pin "2") (pinfunction "2_2") (pintype "passive"))
      (node (ref "C59") (pin "2") (pinfunction "2_2") (pintype "passive"))
      (node (ref "C_M3") (pin "1") (pinfunction "1_1") (pintype "passive"))
      (node (ref "Q19") (pin "1") (pinfunction "S_1") (pintype "passive"))
      (node (ref "Q19") (pin "2") (pinfunction "S_2") (pintype "passive"))
      (node (ref "Q19") (pin "3") (pinfunction "S_3") (pintype "passive"))
      (node (ref "Q23") (pin "1") (pinfunction "S_1") (pintype "passive"))
      (node (ref "Q23") (pin "2") (pinfunction "S_2") (pintype "passive"))
      (node (ref "Q23") (pin "3") (pinfunction "S_3") (pintype "passive"))
      (node (ref "Q27") (pin "1") (pinfunction "S_1") (pintype "passive"))
      (node (ref "Q27") (pin "2") (pinfunction "S_2") (pintype "passive"))
      (node (ref "Q27") (pin "3") (pinfunction "S_3") (pintype "passive"))
      (node (ref "R142") (pin "1") (pinfunction "1_1") (pintype "passive"))
      (node (ref "R144") (pin "1") (pinfunction "1_1") (pintype "passive"))
      (node (ref "R146") (pin "1") (pinfunction "1_1") (pintype "passive"))
      (node (ref "U12") (pin "6") (pinfunction "VDD_6") (pintype "power_in"))
      (node (ref "U14") (pin "6") (pinfunction "VDD_6") (pintype "power_in"))
      (node (ref "U20") (pin "6") (pinfunction "VDD_6") (pintype "power_in"))
      (node (ref "U33") (pin "1") (pinfunction "IP+_1") (pintype "passive"))
      (node (ref "U33") (pin "2") (pinfunction "IP+_2") (pintype "passive"))
    )
    (net (code "36") (name "/M3_1") (class "Default")
      (node (ref "U14") (pin "2") (pinfunction "INA_2") (pintype "input"))
    )
    (net (code "37") (name "/M3_2") (class "Default")
      (node (ref "U14") (pin "4") (pinfunction "INB_4") (pintype "input"))
    )
    (net (code "38") (name "/M3_3") (class "Default")
      (node (ref "U20") (pin "2") (pinfunction "INA_2") (pintype "input"))
    )
    (net (code "39") (name "/M3_4") (class "Default")
      (node (ref "U20") (pin "4") (pinfunction "INB_4") (pintype "input"))
    )
    (net (code "40") (name "/M3_5") (class "Default")
      (node (ref "U12") (pin "2") (pinfunction "INA_2") (pintype "input"))
    )
    (net (code "41") (name "/M3_6") (class "Default")
      (node (ref "U12") (pin "4") (pinfunction "INB_4") (pintype "input"))
    )
    (net (code "42") (name "/M4R_12") (class "Default")
      (node (ref "C52") (pin "2") (pinfunction "2_2") (pintype "passive"))
      (node (ref "C53") (pin "2") (pinfunction "2_2") (pintype "passive"))
      (node (ref "C56") (pin "2") (pinfunction "2_2") (pintype "passive"))
      (node (ref "C57") (pin "2") (pinfunction "2_2") (pintype "passive"))
      (node (ref "C60") (pin "2") (pinfunction "2_2") (pintype "passive"))
      (node (ref "C61") (pin "2") (pinfunction "2_2") (pintype "passive"))
      (node (ref "C_M4") (pin "1") (pinfunction "1_1") (pintype "passive"))
      (node (ref "Q20") (pin "1") (pinfunction "S_1") (pintype "passive"))
      (node (ref "Q20") (pin "2") (pinfunction "S_2") (pintype "passive"))
      (node (ref "Q20") (pin "3") (pinfunction "S_3") (pintype "passive"))
      (node (ref "Q24") (pin "1") (pinfunction "S_1") (pintype "passive"))
      (node (ref "Q24") (pin "2") (pinfunction "S_2") (pintype "passive"))
      (node (ref "Q24") (pin "3") (pinfunction "S_3") (pintype "passive"))
      (node (ref "Q28") (pin "1") (pinfunction "S_1") (pintype "passive"))
      (node (ref "Q28") (pin "2") (pinfunction "S_2") (pintype "passive"))
      (node (ref "Q28") (pin "3") (pinfunction "S_3") (pintype "passive"))
      (node (ref "R143") (pin "1") (pinfunction "1_1") (pintype "passive"))
      (node (ref "R145") (pin "1") (pinfunction "1_1") (pintype "passive"))
      (node (ref "R147") (pin "1") (pinfunction "1_1") (pintype "passive"))
      (node (ref "U15") (pin "6") (pinfunction "VDD_6") (pintype "power_in"))
      (node (ref "U17") (pin "6") (pinfunction "VDD_6") (pintype "power_in"))
      (node (ref "U19") (pin "6") (pinfunction "VDD_6") (pintype "power_in"))
      (node (ref "U34") (pin "3") (pinfunction "IP-_3") (pintype "passive"))
      (node (ref "U34") (pin "4") (pinfunction "IP-_4") (pintype "passive"))
    )
    (net (code "43") (name "/M4_1") (class "Default")
      (node (ref "U15") (pin "2") (pinfunction "INA_2") (pintype "input"))
    )
    (net (code "44") (name "/M4_2") (class "Default")
      (node (ref "U15") (pin "4") (pinfunction "INB_4") (pintype "input"))
    )
    (net (code "45") (name "/M4_3") (class "Default")
      (node (ref "U17") (pin "2") (pinfunction "INA_2") (pintype "input"))
    )
    (net (code "46") (name "/M4_4") (class "Default")
      (node (ref "U17") (pin "4") (pinfunction "INB_4") (pintype "input"))
    )
    (net (code "47") (name "/M4_5") (class "Default")
      (node (ref "U19") (pin "2") (pinfunction "INA_2") (pintype "input"))
    )
    (net (code "48") (name "/M4_6") (class "Default")
      (node (ref "U19") (pin "4") (pinfunction "INB_4") (pintype "input"))
    )
    (net (code "49") (name "/O11") (class "Default")
      (node (ref "MOTOR_1") (pin "6") (pinfunction "6_6") (pintype "passive"))
      (node (ref "P5") (pin "6") (pinfunction "6_6") (pintype "passive"))
      (node (ref "P5") (pin "7") (pinfunction "7_7") (pintype "passive"))
      (node (ref "Q16") (pin "5") (pinfunction "D_5") (pintype "passive"))
      (node (ref "Q16") (pin "6") (pinfunction "D_6") (pintype "passive"))
      (node (ref "Q16") (pin "7") (pinfunction "D_7") (pintype "passive"))
      (node (ref "Q16") (pin "8") (pinfunction "D_8") (pintype "passive"))
      (node (ref "Q18") (pin "5") (pinfunction "D_5") (pintype "passive"))
      (node (ref "Q18") (pin "6") (pinfunction "D_6") (pintype "passive"))
      (node (ref "Q18") (pin "7") (pinfunction "D_7") (pintype "passive"))
      (node (ref "Q18") (pin "8") (pinfunction "D_8") (pintype "passive"))
    )
    (net (code "50") (name "/O12") (class "Default")
      (node (ref "MOTOR_1") (pin "7") (pinfunction "7_7") (pintype "passive"))
      (node (ref "P5") (pin "8") (pinfunction "8_8") (pintype "passive"))
      (node (ref "P5") (pin "9") (pinfunction "9_9") (pintype "passive"))
      (node (ref "Q12") (pin "5") (pinfunction "D_5") (pintype "passive"))
      (node (ref "Q12") (pin "6") (pinfunction "D_6") (pintype "passive"))
      (node (ref "Q12") (pin "7") (pinfunction "D_7") (pintype "passive"))
      (node (ref "Q12") (pin "8") (pinfunction "D_8") (pintype "passive"))
      (node (ref "Q14") (pin "5") (pinfunction "D_5") (pintype "passive"))
      (node (ref "Q14") (pin "6") (pinfunction "D_6") (pintype "passive"))
      (node (ref "Q14") (pin "7") (pinfunction "D_7") (pintype "passive"))
      (node (ref "Q14") (pin "8") (pinfunction "D_8") (pintype "passive"))
    )
    (net (code "51") (name "/O13") (class "Default")
      (node (ref "MOTOR_1") (pin "8") (pinfunction "8_8") (pintype "passive"))
      (node (ref "P5") (pin "10") (pinfunction "10_10") (pintype "passive"))
      (node (ref "P5") (pin "11") (pinfunction "11_11") (pintype "passive"))
      (node (ref "Q10") (pin "5") (pinfunction "D_5") (pintype "passive"))
      (node (ref "Q10") (pin "6") (pinfunction "D_6") (pintype "passive"))
      (node (ref "Q10") (pin "7") (pinfunction "D_7") (pintype "passive"))
      (node (ref "Q10") (pin "8") (pinfunction "D_8") (pintype "passive"))
      (node (ref "Q8") (pin "5") (pinfunction "D_5") (pintype "passive"))
      (node (ref "Q8") (pin "6") (pinfunction "D_6") (pintype "passive"))
      (node (ref "Q8") (pin "7") (pinfunction "D_7") (pintype "passive"))
      (node (ref "Q8") (pin "8") (pinfunction "D_8") (pintype "passive"))
    )
    (net (code "52") (name "/O21") (class "Default")
      (node (ref "MOTOR_2") (pin "6") (pinfunction "6_6") (pintype "passive"))
      (node (ref "P6") (pin "6") (pinfunction "6_6") (pintype "passive"))
      (node (ref "P6") (pin "7") (pinfunction "7_7") (pintype "passive"))
      (node (ref "Q15") (pin "5") (pinfunction "D_5") (pintype "passive"))
      (node (ref "Q15") (pin "6") (pinfunction "D_6") (pintype "passive"))
      (node (ref "Q15") (pin "7") (pinfunction "D_7") (pintype "passive"))
      (node (ref "Q15") (pin "8") (pinfunction "D_8") (pintype "passive"))
      (node (ref "Q17") (pin "5") (pinfunction "D_5") (pintype "passive"))
      (node (ref "Q17") (pin "6") (pinfunction "D_6") (pintype "passive"))
      (node (ref "Q17") (pin "7") (pinfunction "D_7") (pintype "passive"))
      (node (ref "Q17") (pin "8") (pinfunction "D_8") (pintype "passive"))
    )
    (net (code "53") (name "/O22") (class "Default")
      (node (ref "MOTOR_2") (pin "7") (pinfunction "7_7") (pintype "passive"))
      (node (ref "P6") (pin "8") (pinfunction "8_8") (pintype "passive"))
      (node (ref "P6") (pin "9") (pinfunction "9_9") (pintype "passive"))
      (node (ref "Q11") (pin "5") (pinfunction "D_5") (pintype "passive"))
      (node (ref "Q11") (pin "6") (pinfunction "D_6") (pintype "passive"))
      (node (ref "Q11") (pin "7") (pinfunction "D_7") (pintype "passive"))
      (node (ref "Q11") (pin "8") (pinfunction "D_8") (pintype "passive"))
      (node (ref "Q13") (pin "5") (pinfunction "D_5") (pintype "passive"))
      (node (ref "Q13") (pin "6") (pinfunction "D_6") (pintype "passive"))
      (node (ref "Q13") (pin "7") (pinfunction "D_7") (pintype "passive"))
      (node (ref "Q13") (pin "8") (pinfunction "D_8") (pintype "passive"))
    )
    (net (code "54") (name "/O23") (class "Default")
      (node (ref "MOTOR_2") (pin "8") (pinfunction "8_8") (pintype "passive"))
      (node (ref "P6") (pin "10") (pinfunction "10_10") (pintype "passive"))
      (node (ref "P6") (pin "11") (pinfunction "11_11") (pintype "passive"))
      (node (ref "Q7") (pin "5") (pinfunction "D_5") (pintype "passive"))
      (node (ref "Q7") (pin "6") (pinfunction "D_6") (pintype "passive"))
      (node (ref "Q7") (pin "7") (pinfunction "D_7") (pintype "passive"))
      (node (ref "Q7") (pin "8") (pinfunction "D_8") (pintype "passive"))
      (node (ref "Q9") (pin "5") (pinfunction "D_5") (pintype "passive"))
      (node (ref "Q9") (pin "6") (pinfunction "D_6") (pintype "passive"))
      (node (ref "Q9") (pin "7") (pinfunction "D_7") (pintype "passive"))
      (node (ref "Q9") (pin "8") (pinfunction "D_8") (pintype "passive"))
    )
    (net (code "55") (name "/O31") (class "Default")
      (node (ref "MOTOR_3") (pin "6") (pinfunction "6_6") (pintype "passive"))
      (node (ref "P7") (pin "6") (pinfunction "6_6") (pintype "passive"))
      (node (ref "P7") (pin "7") (pinfunction "7_7") (pintype "passive"))
      (node (ref "Q27") (pin "5") (pinfunction "D_5") (pintype "passive"))
      (node (ref "Q27") (pin "6") (pinfunction "D_6") (pintype "passive"))
      (node (ref "Q27") (pin "7") (pinfunction "D_7") (pintype "passive"))
      (node (ref "Q27") (pin "8") (pinfunction "D_8") (pintype "passive"))
      (node (ref "Q29") (pin "5") (pinfunction "D_5") (pintype "passive"))
      (node (ref "Q29") (pin "6") (pinfunction "D_6") (pintype "passive"))
      (node (ref "Q29") (pin "7") (pinfunction "D_7") (pintype "passive"))
      (node (ref "Q29") (pin "8") (pinfunction "D_8") (pintype "passive"))
    )
    (net (code "56") (name "/O32") (class "Default")
      (node (ref "MOTOR_3") (pin "7") (pinfunction "7_7") (pintype "passive"))
      (node (ref "P7") (pin "8") (pinfunction "8_8") (pintype "passive"))
      (node (ref "P7") (pin "9") (pinfunction "9_9") (pintype "passive"))
      (node (ref "Q23") (pin "5") (pinfunction "D_5") (pintype "passive"))
      (node (ref "Q23") (pin "6") (pinfunction "D_6") (pintype "passive"))
      (node (ref "Q23") (pin "7") (pinfunction "D_7") (pintype "passive"))
      (node (ref "Q23") (pin "8") (pinfunction "D_8") (pintype "passive"))
      (node (ref "Q25") (pin "5") (pinfunction "D_5") (pintype "passive"))
      (node (ref "Q25") (pin "6") (pinfunction "D_6") (pintype "passive"))
      (node (ref "Q25") (pin "7") (pinfunction "D_7") (pintype "passive"))
      (node (ref "Q25") (pin "8") (pinfunction "D_8") (pintype "passive"))
    )
    (net (code "57") (name "/O33") (class "Default")
      (node (ref "MOTOR_3") (pin "8") (pinfunction "8_8") (pintype "passive"))
      (node (ref "P7") (pin "10") (pinfunction "10_10") (pintype "passive"))
      (node (ref "P7") (pin "11") (pinfunction "11_11") (pintype "passive"))
      (node (ref "Q19") (pin "5") (pinfunction "D_5") (pintype "passive"))
      (node (ref "Q19") (pin "6") (pinfunction "D_6") (pintype "passive"))
      (node (ref "Q19") (pin "7") (pinfunction "D_7") (pintype "passive"))
      (node (ref "Q19") (pin "8") (pinfunction "D_8") (pintype "passive"))
      (node (ref "Q21") (pin "5") (pinfunction "D_5") (pintype "passive"))
      (node (ref "Q21") (pin "6") (pinfunction "D_6") (pintype "passive"))
      (node (ref "Q21") (pin "7") (pinfunction "D_7") (pintype "passive"))
      (node (ref "Q21") (pin "8") (pinfunction "D_8") (pintype "passive"))
    )
    (net (code "58") (name "/O41") (class "Default")
      (node (ref "MOTOR_4") (pin "6") (pinfunction "6_6") (pintype "passive"))
      (node (ref "P8") (pin "6") (pinfunction "6_6") (pintype "passive"))
      (node (ref "P8") (pin "7") (pinfunction "7_7") (pintype "passive"))
      (node (ref "Q28") (pin "5") (pinfunction "D_5") (pintype "passive"))
      (node (ref "Q28") (pin "6") (pinfunction "D_6") (pintype "passive"))
      (node (ref "Q28") (pin "7") (pinfunction "D_7") (pintype "passive"))
      (node (ref "Q28") (pin "8") (pinfunction "D_8") (pintype "passive"))
      (node (ref "Q30") (pin "5") (pinfunction "D_5") (pintype "passive"))
      (node (ref "Q30") (pin "6") (pinfunction "D_6") (pintype "passive"))
      (node (ref "Q30") (pin "7") (pinfunction "D_7") (pintype "passive"))
      (node (ref "Q30") (pin "8") (pinfunction "D_8") (pintype "passive"))
    )
    (net (code "59") (name "/O42") (class "Default")
      (node (ref "MOTOR_4") (pin "7") (pinfunction "7_7") (pintype "passive"))
      (node (ref "P8") (pin "8") (pinfunction "8_8") (pintype "passive"))
      (node (ref "P8") (pin "9") (pinfunction "9_9") (pintype "passive"))
      (node (ref "Q24") (pin "5") (pinfunction "D_5") (pintype "passive"))
      (node (ref "Q24") (pin "6") (pinfunction "D_6") (pintype "passive"))
      (node (ref "Q24") (pin "7") (pinfunction "D_7") (pintype "passive"))
      (node (ref "Q24") (pin "8") (pinfunction "D_8") (pintype "passive"))
      (node (ref "Q26") (pin "5") (pinfunction "D_5") (pintype "passive"))
      (node (ref "Q26") (pin "6") (pinfunction "D_6") (pintype "passive"))
      (node (ref "Q26") (pin "7") (pinfunction "D_7") (pintype "passive"))
      (node (ref "Q26") (pin "8") (pinfunction "D_8") (pintype "passive"))
    )
    (net (code "60") (name "/O43") (class "Default")
      (node (ref "MOTOR_4") (pin "8") (pinfunction "8_8") (pintype "passive"))
      (node (ref "P8") (pin "10") (pinfunction "10_10") (pintype "passive"))
      (node (ref "P8") (pin "11") (pinfunction "11_11") (pintype "passive"))
      (node (ref "Q20") (pin "5") (pinfunction "D_5") (pintype "passive"))
      (node (ref "Q20") (pin "6") (pinfunction "D_6") (pintype "passive"))
      (node (ref "Q20") (pin "7") (pinfunction "D_7") (pintype "passive"))
      (node (ref "Q20") (pin "8") (pinfunction "D_8") (pintype "passive"))
      (node (ref "Q22") (pin "5") (pinfunction "D_5") (pintype "passive"))
      (node (ref "Q22") (pin "6") (pinfunction "D_6") (pintype "passive"))
      (node (ref "Q22") (pin "7") (pinfunction "D_7") (pintype "passive"))
      (node (ref "Q22") (pin "8") (pinfunction "D_8") (pintype "passive"))
    )
    (net (code "65") (name "GND") (class "Default")
      (node (ref "C113") (pin "2") (pinfunction "2_2") (pintype "passive"))
      (node (ref "C114") (pin "2") (pinfunction "2_2") (pintype "passive"))
      (node (ref "C115") (pin "2") (pinfunction "2_2") (pintype "passive"))
      (node (ref "C116") (pin "2") (pinfunction "2_2") (pintype "passive"))
      (node (ref "C117") (pin "2") (pinfunction "2_2") (pintype "passive"))
      (node (ref "C118") (pin "2") (pinfunction "2_2") (pintype "passive"))
      (node (ref "C119") (pin "2") (pinfunction "2_2") (pintype "passive"))
      (node (ref "C121") (pin "2") (pinfunction "2_2") (pintype "passive"))
      (node (ref "C30") (pin "1") (pinfunction "1_1") (pintype "passive"))
      (node (ref "C32") (pin "1") (pinfunction "1_1") (pintype "passive"))
      (node (ref "C40") (pin "1") (pinfunction "1_1") (pintype "passive"))
      (node (ref "C41") (pin "1") (pinfunction "1_1") (pintype "passive"))
      (node (ref "C42") (pin "1") (pinfunction "1_1") (pintype "passive"))
      (node (ref "C43") (pin "1") (pinfunction "1_1") (pintype "passive"))
      (node (ref "C44") (pin "1") (pinfunction "1_1") (pintype "passive"))
      (node (ref "C45") (pin "1") (pinfunction "1_1") (pintype "passive"))
      (node (ref "C46") (pin "1") (pinfunction "1_1") (pintype "passive"))
      (node (ref "C47") (pin "1") (pinfunction "1_1") (pintype "passive"))
      (node (ref "C48") (pin "1") (pinfunction "1_1") (pintype "passive"))
      (node (ref "C49") (pin "1") (pinfunction "1_1") (pintype "passive"))
      (node (ref "C50") (pin "1") (pinfunction "1_1") (pintype "passive"))
      (node (ref "C51") (pin "1") (pinfunction "1_1") (pintype "passive"))
      (node (ref "C52") (pin "1") (pinfunction "1_1") (pintype "passive"))
      (node (ref "C53") (pin "1") (pinfunction "1_1") (pintype "passive"))
      (node (ref "C54") (pin "1") (pinfunction "1_1") (pintype "passive"))
      (node (ref "C55") (pin "1") (pinfunction "1_1") (pintype "passive"))
      (node (ref "C56") (pin "1") (pinfunction "1_1") (pintype "passive"))
      (node (ref "C57") (pin "1") (pinfunction "1_1") (pintype "passive"))
      (node (ref "C58") (pin "1") (pinfunction "1_1") (pintype "passive"))
      (node (ref "C59") (pin "1") (pinfunction "1_1") (pintype "passive"))
      (node (ref "C60") (pin "1") (pinfunction "1_1") (pintype "passive"))
      (node (ref "C61") (pin "1") (pinfunction "1_1") (pintype "passive"))
      (node (ref "C_M1") (pin "2") (pinfunction "2_2") (pintype "passive"))
      (node (ref "C_M2") (pin "2") (pinfunction "2_2") (pintype "passive"))
      (node (ref "C_M3") (pin "2") (pinfunction "2_2") (pintype "passive"))
      (node (ref "C_M4") (pin "2") (pinfunction "2_2") (pintype "passive"))
      (node (ref "MOTOR_1") (pin "4") (pinfunction "4_4") (pintype "passive"))
      (node (ref "MOTOR_2") (pin "4") (pinfunction "4_4") (pintype "passive"))
      (node (ref "MOTOR_3") (pin "4") (pinfunction "4_4") (pintype "passive"))
      (node (ref "MOTOR_4") (pin "4") (pinfunction "4_4") (pintype "passive"))
      (node (ref "P5") (pin "12") (pinfunction "12_12") (pintype "passive"))
      (node (ref "P5") (pin "5") (pinfunction "5_5") (pintype "passive"))
      (node (ref "P6") (pin "12") (pinfunction "12_12") (pintype "passive"))
      (node (ref "P6") (pin "5") (pinfunction "5_5") (pintype "passive"))
      (node (ref "P7") (pin "12") (pinfunction "12_12") (pintype "passive"))
      (node (ref "P7") (pin "5") (pinfunction "5_5") (pintype "passive"))
      (node (ref "P8") (pin "12") (pinfunction "12_12") (pintype "passive"))
      (node (ref "P8") (pin "5") (pinfunction "5_5") (pintype "passive"))
      (node (ref "Q10") (pin "1") (pinfunction "S_1") (pintype "passive"))
      (node (ref "Q10") (pin "2") (pinfunction "S_2") (pintype "passive"))
      (node (ref "Q10") (pin "3") (pinfunction "S_3") (pintype "passive"))
      (node (ref "Q13") (pin "1") (pinfunction "S_1") (pintype "passive"))
      (node (ref "Q13") (pin "2") (pinfunction "S_2") (pintype "passive"))
      (node (ref "Q13") (pin "3") (pinfunction "S_3") (pintype "passive"))
      (node (ref "Q14") (pin "1") (pinfunction "S_1") (pintype "passive"))
      (node (ref "Q14") (pin "2") (pinfunction "S_2") (pintype "passive"))
      (node (ref "Q14") (pin "3") (pinfunction "S_3") (pintype "passive"))
      (node (ref "Q17") (pin "1") (pinfunction "S_1") (pintype "passive"))
      (node (ref "Q17") (pin "2") (pinfunction "S_2") (pintype "passive"))
      (node (ref "Q17") (pin "3") (pinfunction "S_3") (pintype "passive"))
      (node (ref "Q18") (pin "1") (pinfunction "S_1") (pintype "passive"))
      (node (ref "Q18") (pin "2") (pinfunction "S_2") (pintype "passive"))
      (node (ref "Q18") (pin "3") (pinfunction "S_3") (pintype "passive"))
      (node (ref "Q21") (pin "1") (pinfunction "S_1") (pintype "passive"))
      (node (ref "Q21") (pin "2") (pinfunction "S_2") (pintype "passive"))
      (node (ref "Q21") (pin "3") (pinfunction "S_3") (pintype "passive"))
      (node (ref "Q22") (pin "1") (pinfunction "S_1") (pintype "passive"))
      (node (ref "Q22") (pin "2") (pinfunction "S_2") (pintype "passive"))
      (node (ref "Q22") (pin "3") (pinfunction "S_3") (pintype "passive"))
      (node (ref "Q25") (pin "1") (pinfunction "S_1") (pintype "passive"))
      (node (ref "Q25") (pin "2") (pinfunction "S_2") (pintype "passive"))
      (node (ref "Q25") (pin "3") (pinfunction "S_3") (pintype "passive"))
      (node (ref "Q26") (pin "1") (pinfunction "S_1") (pintype "passive"))
      (node (ref "Q26") (pin "2") (pinfunction "S_2") (pintype "passive"))
      (node (ref "Q26") (pin "3") (pinfunction "S_3") (pintype "passive"))
      (node (ref "Q29") (pin "1") (pinfunction "S_1") (pintype "passive"))
      (node (ref "Q29") (pin "2") (pinfunction "S_2") (pintype "passive"))
      (node (ref "Q29") (pin "3") (pinfunction "S_3") (pintype "passive"))
      (node (ref "Q30") (pin "1") (pinfunction "S_1") (pintype "passive"))
      (node (ref "Q30") (pin "2") (pinfunction "S_2") (pintype "passive"))
      (node (ref "Q30") (pin "3") (pinfunction "S_3") (pintype "passive"))
      (node (ref "Q9") (pin "1") (pinfunction "S_1") (pintype "passive"))
      (node (ref "Q9") (pin "2") (pinfunction "S_2") (pintype "passive"))
      (node (ref "Q9") (pin "3") (pinfunction "S_3") (pintype "passive"))
      (node (ref "U11") (pin "3") (pinfunction "GND_3") (pintype "power_in"))
      (node (ref "U12") (pin "3") (pinfunction "GND_3") (pintype "power_in"))
      (node (ref "U13") (pin "3") (pinfunction "GND_3") (pintype "power_in"))
      (node (ref "U14") (pin "3") (pinfunction "GND_3") (pintype "power_in"))
      (node (ref "U15") (pin "3") (pinfunction "GND_3") (pintype "power_in"))
      (node (ref "U16") (pin "3") (pinfunction "GND_3") (pintype "power_in"))
      (node (ref "U17") (pin "3") (pinfunction "GND_3") (pintype "power_in"))
      (node (ref "U18") (pin "3") (pinfunction "GND_3") (pintype "power_in"))
      (node (ref "U19") (pin "3") (pinfunction "GND_3") (pintype "power_in"))
      (node (ref "U20") (pin "3") (pinfunction "GND_3") (pintype "power_in"))
      (node (ref "U31") (pin "5") (pinfunction "GND_5") (pintype "passive"))
      (node (ref "U32") (pin "5") (pinfunction "GND_5") (pintype "passive"))
      (node (ref "U33") (pin "5") (pinfunction "GND_5") (pintype "passive"))
      (node (ref "U34") (pin "5") (pinfunction "GND_5") (pintype "passive"))
      (node (ref "U6") (pin "3") (pinfunction "GND_3") (pintype "power_in"))
      (node (ref "U9") (pin "3") (pinfunction "GND_3") (pintype "power_in"))
    )
    (net (code "66") (name "Net-(Q7-G)") (class "Default")
      (node (ref "Q7") (pin "4") (pinfunction "G_4") (pintype "passive"))
      (node (ref "R136") (pin "2") (pinfunction "2_2") (pintype "passive"))
      (node (ref "R59") (pin "2") (pinfunction "2_2") (pintype "passive"))
    )
    (net (code "67") (name "Net-(Q8-G)") (class "Default")
      (node (ref "Q8") (pin "4") (pinfunction "G_4") (pintype "passive"))
      (node (ref "R137") (pin "2") (pinfunction "2_2") (pintype "passive"))
      (node (ref "R60") (pin "2") (pinfunction "2_2") (pintype "passive"))
    )
    (net (code "68") (name "Net-(Q9-G)") (class "Default")
      (node (ref "Q9") (pin "4") (pinfunction "G_4") (pintype "passive"))
      (node (ref "R61") (pin "2") (pinfunction "2_2") (pintype "passive"))
    )
    (net (code "69") (name "Net-(Q10-G)") (class "Default")
      (node (ref "Q10") (pin "4") (pinfunction "G_4") (pintype "passive"))
      (node (ref "R62") (pin "2") (pinfunction "2_2") (pintype "passive"))
    )
    (net (code "70") (name "Net-(Q11-G)") (class "Default")
      (node (ref "Q11") (pin "4") (pinfunction "G_4") (pintype "passive"))
      (node (ref "R138") (pin "2") (pinfunction "2_2") (pintype "passive"))
      (node (ref "R65") (pin "2") (pinfunction "2_2") (pintype "passive"))
    )
    (net (code "71") (name "Net-(Q12-G)") (class "Default")
      (node (ref "Q12") (pin "4") (pinfunction "G_4") (pintype "passive"))
      (node (ref "R139") (pin "2") (pinfunction "2_2") (pintype "passive"))
      (node (ref "R66") (pin "2") (pinfunction "2_2") (pintype "passive"))
    )
    (net (code "72") (name "Net-(Q13-G)") (class "Default")
      (node (ref "Q13") (pin "4") (pinfunction "G_4") (pintype "passive"))
      (node (ref "R67") (pin "2") (pinfunction "2_2") (pintype "passive"))
    )
    (net (code "73") (name "Net-(Q14-G)") (class "Default")
      (node (ref "Q14") (pin "4") (pinfunction "G_4") (pintype "passive"))
      (node (ref "R68") (pin "2") (pinfunction "2_2") (pintype "passive"))
    )
    (net (code "74") (name "Net-(Q15-G)") (class "Default")
      (node (ref "Q15") (pin "4") (pinfunction "G_4") (pintype "passive"))
      (node (ref "R140") (pin "2") (pinfunction "2_2") (pintype "passive"))
      (node (ref "R71") (pin "2") (pinfunction "2_2") (pintype "passive"))
    )
    (net (code "75") (name "Net-(Q16-G)") (class "Default")
      (node (ref "Q16") (pin "4") (pinfunction "G_4") (pintype "passive"))
      (node (ref "R141") (pin "2") (pinfunction "2_2") (pintype "passive"))
      (node (ref "R72") (pin "2") (pinfunction "2_2") (pintype "passive"))
    )
    (net (code "76") (name "Net-(Q17-G)") (class "Default")
      (node (ref "Q17") (pin "4") (pinfunction "G_4") (pintype "passive"))
      (node (ref "R73") (pin "2") (pinfunction "2_2") (pintype "passive"))
    )
    (net (code "77") (name "Net-(Q18-G)") (class "Default")
      (node (ref "Q18") (pin "4") (pinfunction "G_4") (pintype "passive"))
      (node (ref "R74") (pin "2") (pinfunction "2_2") (pintype "passive"))
    )
    (net (code "78") (name "Net-(Q19-G)") (class "Default")
      (node (ref "Q19") (pin "4") (pinfunction "G_4") (pintype "passive"))
      (node (ref "R142") (pin "2") (pinfunction "2_2") (pintype "passive"))
      (node (ref "R77") (pin "2") (pinfunction "2_2") (pintype "passive"))
    )
    (net (code "79") (name "Net-(Q20-G)") (class "Default")
      (node (ref "Q20") (pin "4") (pinfunction "G_4") (pintype "passive"))
      (node (ref "R143") (pin "2") (pinfunction "2_2") (pintype "passive"))
      (node (ref "R78") (pin "2") (pinfunction "2_2") (pintype "passive"))
    )
    (net (code "80") (name "Net-(Q21-G)") (class "Default")
      (node (ref "Q21") (pin "4") (pinfunction "G_4") (pintype "passive"))
      (node (ref "R79") (pin "2") (pinfunction "2_2") (pintype "passive"))
    )
    (net (code "81") (name "Net-(Q22-G)") (class "Default")
      (node (ref "Q22") (pin "4") (pinfunction "G_4") (pintype "passive"))
      (node (ref "R80") (pin "2") (pinfunction "2_2") (pintype "passive"))
    )
    (net (code "82") (name "Net-(Q23-G)") (class "Default")
      (node (ref "Q23") (pin "4") (pinfunction "G_4") (pintype "passive"))
      (node (ref "R144") (pin "2") (pinfunction "2_2") (pintype "passive"))
      (node (ref "R83") (pin "2") (pinfunction "2_2") (pintype "passive"))
    )
    (net (code "83") (name "Net-(Q24-G)") (class "Default")
      (node (ref "Q24") (pin "4") (pinfunction "G_4") (pintype "passive"))
      (node (ref "R145") (pin "2") (pinfunction "2_2") (pintype "passive"))
      (node (ref "R84") (pin "2") (pinfunction "2_2") (pintype "passive"))
    )
    (net (code "84") (name "Net-(Q25-G)") (class "Default")
      (node (ref "Q25") (pin "4") (pinfunction "G_4") (pintype "passive"))
      (node (ref "R85") (pin "2") (pinfunction "2_2") (pintype "passive"))
    )
    (net (code "85") (name "Net-(Q26-G)") (class "Default")
      (node (ref "Q26") (pin "4") (pinfunction "G_4") (pintype "passive"))
      (node (ref "R86") (pin "2") (pinfunction "2_2") (pintype "passive"))
    )
    (net (code "86") (name "Net-(Q27-G)") (class "Default")
      (node (ref "Q27") (pin "4") (pinfunction "G_4") (pintype "passive"))
      (node (ref "R146") (pin "2") (pinfunction "2_2") (pintype "passive"))
      (node (ref "R89") (pin "2") (pinfunction "2_2") (pintype "passive"))
    )
    (net (code "87") (name "Net-(Q28-G)") (class "Default")
      (node (ref "Q28") (pin "4") (pinfunction "G_4") (pintype "passive"))
      (node (ref "R147") (pin "2") (pinfunction "2_2") (pintype "passive"))
      (node (ref "R90") (pin "2") (pinfunction "2_2") (pintype "passive"))
    )
    (net (code "88") (name "Net-(Q29-G)") (class "Default")
      (node (ref "Q29") (pin "4") (pinfunction "G_4") (pintype "passive"))
      (node (ref "R91") (pin "2") (pinfunction "2_2") (pintype "passive"))
    )
    (net (code "89") (name "Net-(Q30-G)") (class "Default")
      (node (ref "Q30") (pin "4") (pinfunction "G_4") (pintype "passive"))
      (node (ref "R92") (pin "2") (pinfunction "2_2") (pintype "passive"))
    )
    (net (code "90") (name "Net-(U6-OUTA)") (class "Default")
      (node (ref "R59") (pin "1") (pinfunction "1_1") (pintype "passive"))
      (node (ref "U6") (pin "7") (pinfunction "OUTA_7") (pintype "output"))
    )
    (net (code "91") (name "Net-(U6-OUTB)") (class "Default")
      (node (ref "R61") (pin "1") (pinfunction "1_1") (pintype "passive"))
      (node (ref "U6") (pin "5") (pinfunction "OUTB_5") (pintype "output"))
    )
    (net (code "92") (name "Net-(U9-OUTA)") (class "Default")
      (node (ref "R60") (pin "1") (pinfunction "1_1") (pintype "passive"))
      (node (ref "U9") (pin "7") (pinfunction "OUTA_7") (pintype "output"))
    )
    (net (code "93") (name "Net-(U9-OUTB)") (class "Default")
      (node (ref "R62") (pin "1") (pinfunction "1_1") (pintype "passive"))
      (node (ref "U9") (pin "5") (pinfunction "OUTB_5") (pintype "output"))
    )
    (net (code "94") (name "Net-(U11-OUTA)") (class "Default")
      (node (ref "R66") (pin "1") (pinfunction "1_1") (pintype "passive"))
      (node (ref "U11") (pin "7") (pinfunction "OUTA_7") (pintype "output"))
    )
    (net (code "95") (name "Net-(U11-OUTB)") (class "Default")
      (node (ref "R68") (pin "1") (pinfunction "1_1") (pintype "passive"))
      (node (ref "U11") (pin "5") (pinfunction "OUTB_5") (pintype "output"))
    )
    (net (code "96") (name "Net-(U12-OUTA)") (class "Default")
      (node (ref "R77") (pin "1") (pinfunction "1_1") (pintype "passive"))
      (node (ref "U12") (pin "7") (pinfunction "OUTA_7") (pintype "output"))
    )
    (net (code "97") (name "Net-(U12-OUTB)") (class "Default")
      (node (ref "R79") (pin "1") (pinfunction "1_1") (pintype "passive"))
      (node (ref "U12") (pin "5") (pinfunction "OUTB_5") (pintype "output"))
    )
    (net (code "98") (name "Net-(U13-OUTA)") (class "Default")
      (node (ref "R72") (pin "1") (pinfunction "1_1") (pintype "passive"))
      (node (ref "U13") (pin "7") (pinfunction "OUTA_7") (pintype "output"))
    )
    (net (code "99") (name "Net-(U13-OUTB)") (class "Default")
      (node (ref "R74") (pin "1") (pinfunction "1_1") (pintype "passive"))
      (node (ref "U13") (pin "5") (pinfunction "OUTB_5") (pintype "output"))
    )
    (net (code "100") (name "Net-(U14-OUTA)") (class "Default")
      (node (ref "R83") (pin "1") (pinfunction "1_1") (pintype "passive"))
      (node (ref "U14") (pin "7") (pinfunction "OUTA_7") (pintype "output"))
    )
    (net (code "101") (name "Net-(U14-OUTB)") (class "Default")
      (node (ref "R85") (pin "1") (pinfunction "1_1") (pintype "passive"))
      (node (ref "U14") (pin "5") (pinfunction "OUTB_5") (pintype "output"))
    )
    (net (code "102") (name "Net-(U15-OUTA)") (class "Default")
      (node (ref "R78") (pin "1") (pinfunction "1_1") (pintype "passive"))
      (node (ref "U15") (pin "7") (pinfunction "OUTA_7") (pintype "output"))
    )
    (net (code "103") (name "Net-(U15-OUTB)") (class "Default")
      (node (ref "R80") (pin "1") (pinfunction "1_1") (pintype "passive"))
      (node (ref "U15") (pin "5") (pinfunction "OUTB_5") (pintype "output"))
    )
    (net (code "104") (name "Net-(U16-OUTA)") (class "Default")
      (node (ref "R65") (pin "1") (pinfunction "1_1") (pintype "passive"))
      (node (ref "U16") (pin "7") (pinfunction "OUTA_7") (pintype "output"))
    )
    (net (code "105") (name "Net-(U16-OUTB)") (class "Default")
      (node (ref "R67") (pin "1") (pinfunction "1_1") (pintype "passive"))
      (node (ref "U16") (pin "5") (pinfunction "OUTB_5") (pintype "output"))
    )
    (net (code "106") (name "Net-(U17-OUTA)") (class "Default")
      (node (ref "R84") (pin "1") (pinfunction "1_1") (pintype "passive"))
      (node (ref "U17") (pin "7") (pinfunction "OUTA_7") (pintype "output"))
    )
    (net (code "107") (name "Net-(U17-OUTB)") (class "Default")
      (node (ref "R86") (pin "1") (pinfunction "1_1") (pintype "passive"))
      (node (ref "U17") (pin "5") (pinfunction "OUTB_5") (pintype "output"))
    )
    (net (code "108") (name "Net-(U18-OUTA)") (class "Default")
      (node (ref "R71") (pin "1") (pinfunction "1_1") (pintype "passive"))
      (node (ref "U18") (pin "7") (pinfunction "OUTA_7") (pintype "output"))
    )
    (net (code "109") (name "Net-(U18-OUTB)") (class "Default")
      (node (ref "R73") (pin "1") (pinfunction "1_1") (pintype "passive"))
      (node (ref "U18") (pin "5") (pinfunction "OUTB_5") (pintype "output"))
    )
    (net (code "110") (name "Net-(U19-OUTA)") (class "Default")
      (node (ref "R90") (pin "1") (pinfunction "1_1") (pintype "passive"))
      (node (ref "U19") (pin "7") (pinfunction "OUTA_7") (pintype "output"))
    )
    (net (code "111") (name "Net-(U19-OUTB)") (class "Default")
      (node (ref "R92") (pin "1") (pinfunction "1_1") (pintype "passive"))
      (node (ref "U19") (pin "5") (pinfunction "OUTB_5") (pintype "output"))
    )
    (net (code "112") (name "Net-(U20-OUTA)") (class "Default")
      (node (ref "R89") (pin "1") (pinfunction "1_1") (pintype "passive"))
      (node (ref "U20") (pin "7") (pinfunction "OUTA_7") (pintype "output"))
    )
    (net (code "113") (name "Net-(U20-OUTB)") (class "Default")
      (node (ref "R91") (pin "1") (pinfunction "1_1") (pintype "passive"))
      (node (ref "U20") (pin "5") (pinfunction "OUTB_5") (pintype "output"))
    )
    (net (code "114") (name "Net-(U31-FILTER)") (class "Default")
      (node (ref "C115") (pin "1") (pinfunction "1_1") (pintype "passive"))
      (node (ref "U31") (pin "6") (pinfunction "FILTER_6") (pintype "passive"))
    )
    (net (code "115") (name "Net-(U32-FILTER)") (class "Default")
      (node (ref "C116") (pin "1") (pinfunction "1_1") (pintype "passive"))
      (node (ref "U32") (pin "6") (pinfunction "FILTER_6") (pintype "passive"))
    )
    (net (code "116") (name "Net-(U33-FILTER)") (class "Default")
      (node (ref "C119") (pin "1") (pinfunction "1_1") (pintype "passive"))
      (node (ref "U33") (pin "6") (pinfunction "FILTER_6") (pintype "passive"))
    )
    (net (code "117") (name "Net-(U34-FILTER)") (class "Default")
      (node (ref "C121") (pin "1") (pinfunction "1_1") (pintype "passive"))
      (node (ref "U34") (pin "6") (pinfunction "FILTER_6") (pintype "passive"))
    )
    (net (code "118") (name "V 12") (class "Default")
      (node (ref "U31") (pin "1") (pinfunction "IP+_1") (pintype "passive"))
      (node (ref "U31") (pin "2") (pinfunction "IP+_2") (pintype "passive"))
      (node (ref "U32") (pin "3") (pinfunction "IP-_3") (pintype "passive"))
      (node (ref "U32") (pin "4") (pinfunction "IP-_4") (pintype "passive"))
      (node (ref "U33") (pin "3") (pinfunction "IP-_3") (pintype "passive"))
      (node (ref "U33") (pin "4") (pinfunction "IP-_4") (pintype "passive"))
      (node (ref "U34") (pin "1") (pinfunction "IP+_1") (pintype "passive"))
      (node (ref "U34") (pin "2") (pinfunction "IP+_2") (pintype "passive"))
    )
    (net (code "119") (name "VCC") (class "Default")
      (node (ref "C113") (pin "1") (pinfunction "1_1") (pintype "passive"))
      (node (ref "C114") (pin "1") (pinfunction "1_1") (pintype "passive"))
      (node (ref "C117") (pin "1") (pinfunction "1_1") (pintype "passive"))
      (node (ref "C118") (pin "1") (pinfunction "1_1") (pintype "passive"))
      (node (ref "MOTOR_1") (pin "5") (pinfunction "5_5") (pintype "passive"))
      (node (ref "MOTOR_2") (pin "5") (pinfunction "5_5") (pintype "passive"))
      (node (ref "MOTOR_3") (pin "5") (pinfunction "5_5") (pintype "passive"))
      (node (ref "MOTOR_4") (pin "5") (pinfunction "5_5") (pintype "passive"))
      (node (ref "P5") (pin "1") (pinfunction "1_1") (pintype "passive"))
      (node (ref "P6") (pin "1") (pinfunction "1_1") (pintype "passive"))
      (node (ref "P7") (pin "1") (pinfunction "1_1") (pintype "passive"))
      (node (ref "P8") (pin "1") (pinfunction "1_1") (pintype "passive"))
      (node (ref "U31") (pin "8") (pinfunction "VCC_8") (pintype "passive"))
      (node (ref "U32") (pin "8") (pinfunction "VCC_8") (pintype "passive"))
      (node (ref "U33") (pin "8") (pinfunction "VCC_8") (pintype "passive"))
      (node (ref "U34") (pin "8") (pinfunction "VCC_8") (pintype "passive"))
    )
    (net (code "120") (name "unconnected-(U6-NC-Pad1)") (class "Default")
      (node (ref "U6") (pin "1") (pinfunction "NC_1") (pintype "passive"))
    )
    (net (code "121") (name "unconnected-(U6-NC-Pad8)") (class "Default")
      (node (ref "U6") (pin "8") (pinfunction "NC_8") (pintype "passive"))
    )
    (net (code "122") (name "unconnected-(U9-NC-Pad1)") (class "Default")
      (node (ref "U9") (pin "1") (pinfunction "NC_1") (pintype "passive"))
    )
    (net (code "123") (name "unconnected-(U9-NC-Pad8)") (class "Default")
      (node (ref "U9") (pin "8") (pinfunction "NC_8") (pintype "passive"))
    )
    (net (code "124") (name "unconnected-(U11-NC-Pad1)") (class "Default")
      (node (ref "U11") (pin "1") (pinfunction "NC_1") (pintype "passive"))
    )
    (net (code "125") (name "unconnected-(U11-NC-Pad8)") (class "Default")
      (node (ref "U11") (pin "8") (pinfunction "NC_8") (pintype "passive"))
    )
    (net (code "126") (name "unconnected-(U12-NC-Pad1)") (class "Default")
      (node (ref "U12") (pin "1") (pinfunction "NC_1") (pintype "passive"))
    )
    (net (code "127") (name "unconnected-(U12-NC-Pad8)") (class "Default")
      (node (ref "U12") (pin "8") (pinfunction "NC_8") (pintype "passive"))
    )
    (net (code "128") (name "unconnected-(U13-NC-Pad1)") (class "Default")
      (node (ref "U13") (pin "1") (pinfunction "NC_1") (pintype "passive"))
    )
    (net (code "129") (name "unconnected-(U13-NC-Pad8)") (class "Default")
      (node (ref "U13") (pin "8") (pinfunction "NC_8") (pintype "passive"))
    )
    (net (code "130") (name "unconnected-(U14-NC-Pad1)") (class "Default")
      (node (ref "U14") (pin "1") (pinfunction "NC_1") (pintype "passive"))
    )
    (net (code "131") (name "unconnected-(U14-NC-Pad8)") (class "Default")
      (node (ref "U14") (pin "8") (pinfunction "NC_8") (pintype "passive"))
    )
    (net (code "132") (name "unconnected-(U15-NC-Pad1)") (class "Default")
      (node (ref "U15") (pin "1") (pinfunction "NC_1") (pintype "passive"))
    )
    (net (code "133") (name "unconnected-(U15-NC-Pad8)") (class "Default")
      (node (ref "U15") (pin "8") (pinfunction "NC_8") (pintype "passive"))
    )
    (net (code "134") (name "unconnected-(U16-NC-Pad1)") (class "Default")
      (node (ref "U16") (pin "1") (pinfunction "NC_1") (pintype "passive"))
    )
    (net (code "135") (name "unconnected-(U16-NC-Pad8)") (class "Default")
      (node (ref "U16") (pin "8") (pinfunction "NC_8") (pintype "passive"))
    )
    (net (code "136") (name "unconnected-(U17-NC-Pad1)") (class "Default")
      (node (ref "U17") (pin "1") (pinfunction "NC_1") (pintype "passive"))
    )
    (net (code "137") (name "unconnected-(U17-NC-Pad8)") (class "Default")
      (node (ref "U17") (pin "8") (pinfunction "NC_8") (pintype "passive"))
    )
    (net (code "138") (name "unconnected-(U18-NC-Pad1)") (class "Default")
      (node (ref "U18") (pin "1") (pinfunction "NC_1") (pintype "passive"))
    )
    (net (code "139") (name "unconnected-(U18-NC-Pad8)") (class "Default")
      (node (ref "U18") (pin "8") (pinfunction "NC_8") (pintype "passive"))
    )
    (net (code "140") (name "unconnected-(U19-NC-Pad1)") (class "Default")
      (node (ref "U19") (pin "1") (pinfunction "NC_1") (pintype "passive"))
    )
    (net (code "141") (name "unconnected-(U19-NC-Pad8)") (class "Default")
      (node (ref "U19") (pin "8") (pinfunction "NC_8") (pintype "passive"))
    )
    (net (code "142") (name "unconnected-(U20-NC-Pad1)") (class "Default")
      (node (ref "U20") (pin "1") (pinfunction "NC_1") (pintype "passive"))
    )
    (net (code "143") (name "unconnected-(U20-NC-Pad8)") (class "Default")
      (node (ref "U20") (pin "8") (pinfunction "NC_8") (pintype "passive"))
    )
  )
)
